# Arche-RoboCore.net
KiCad netlist of a schematic drawn in EAGLE
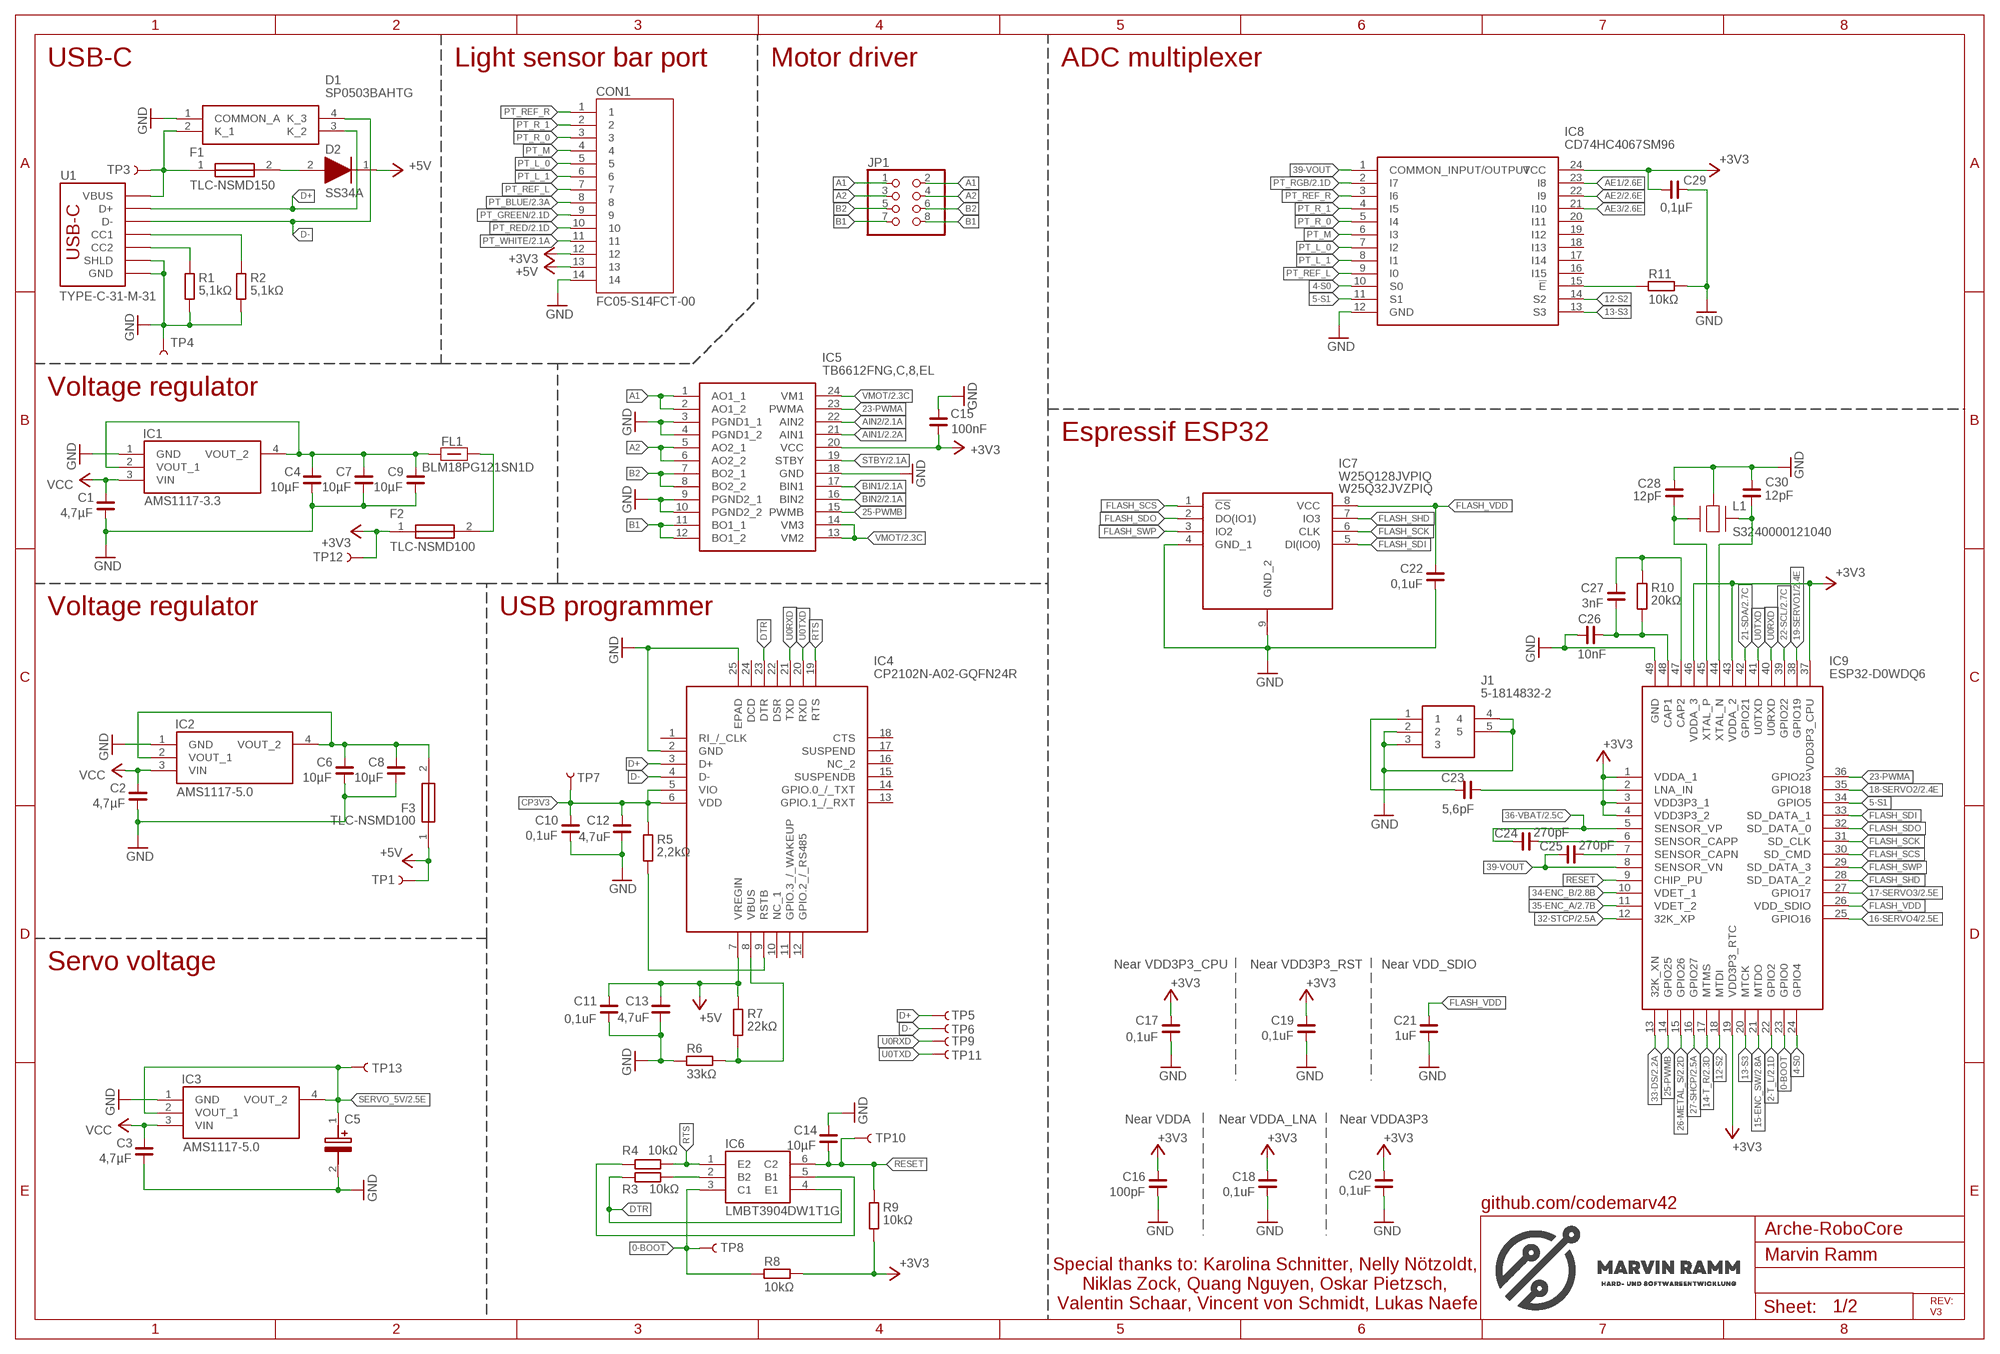
[diagram p0: schematic, sheet 1]
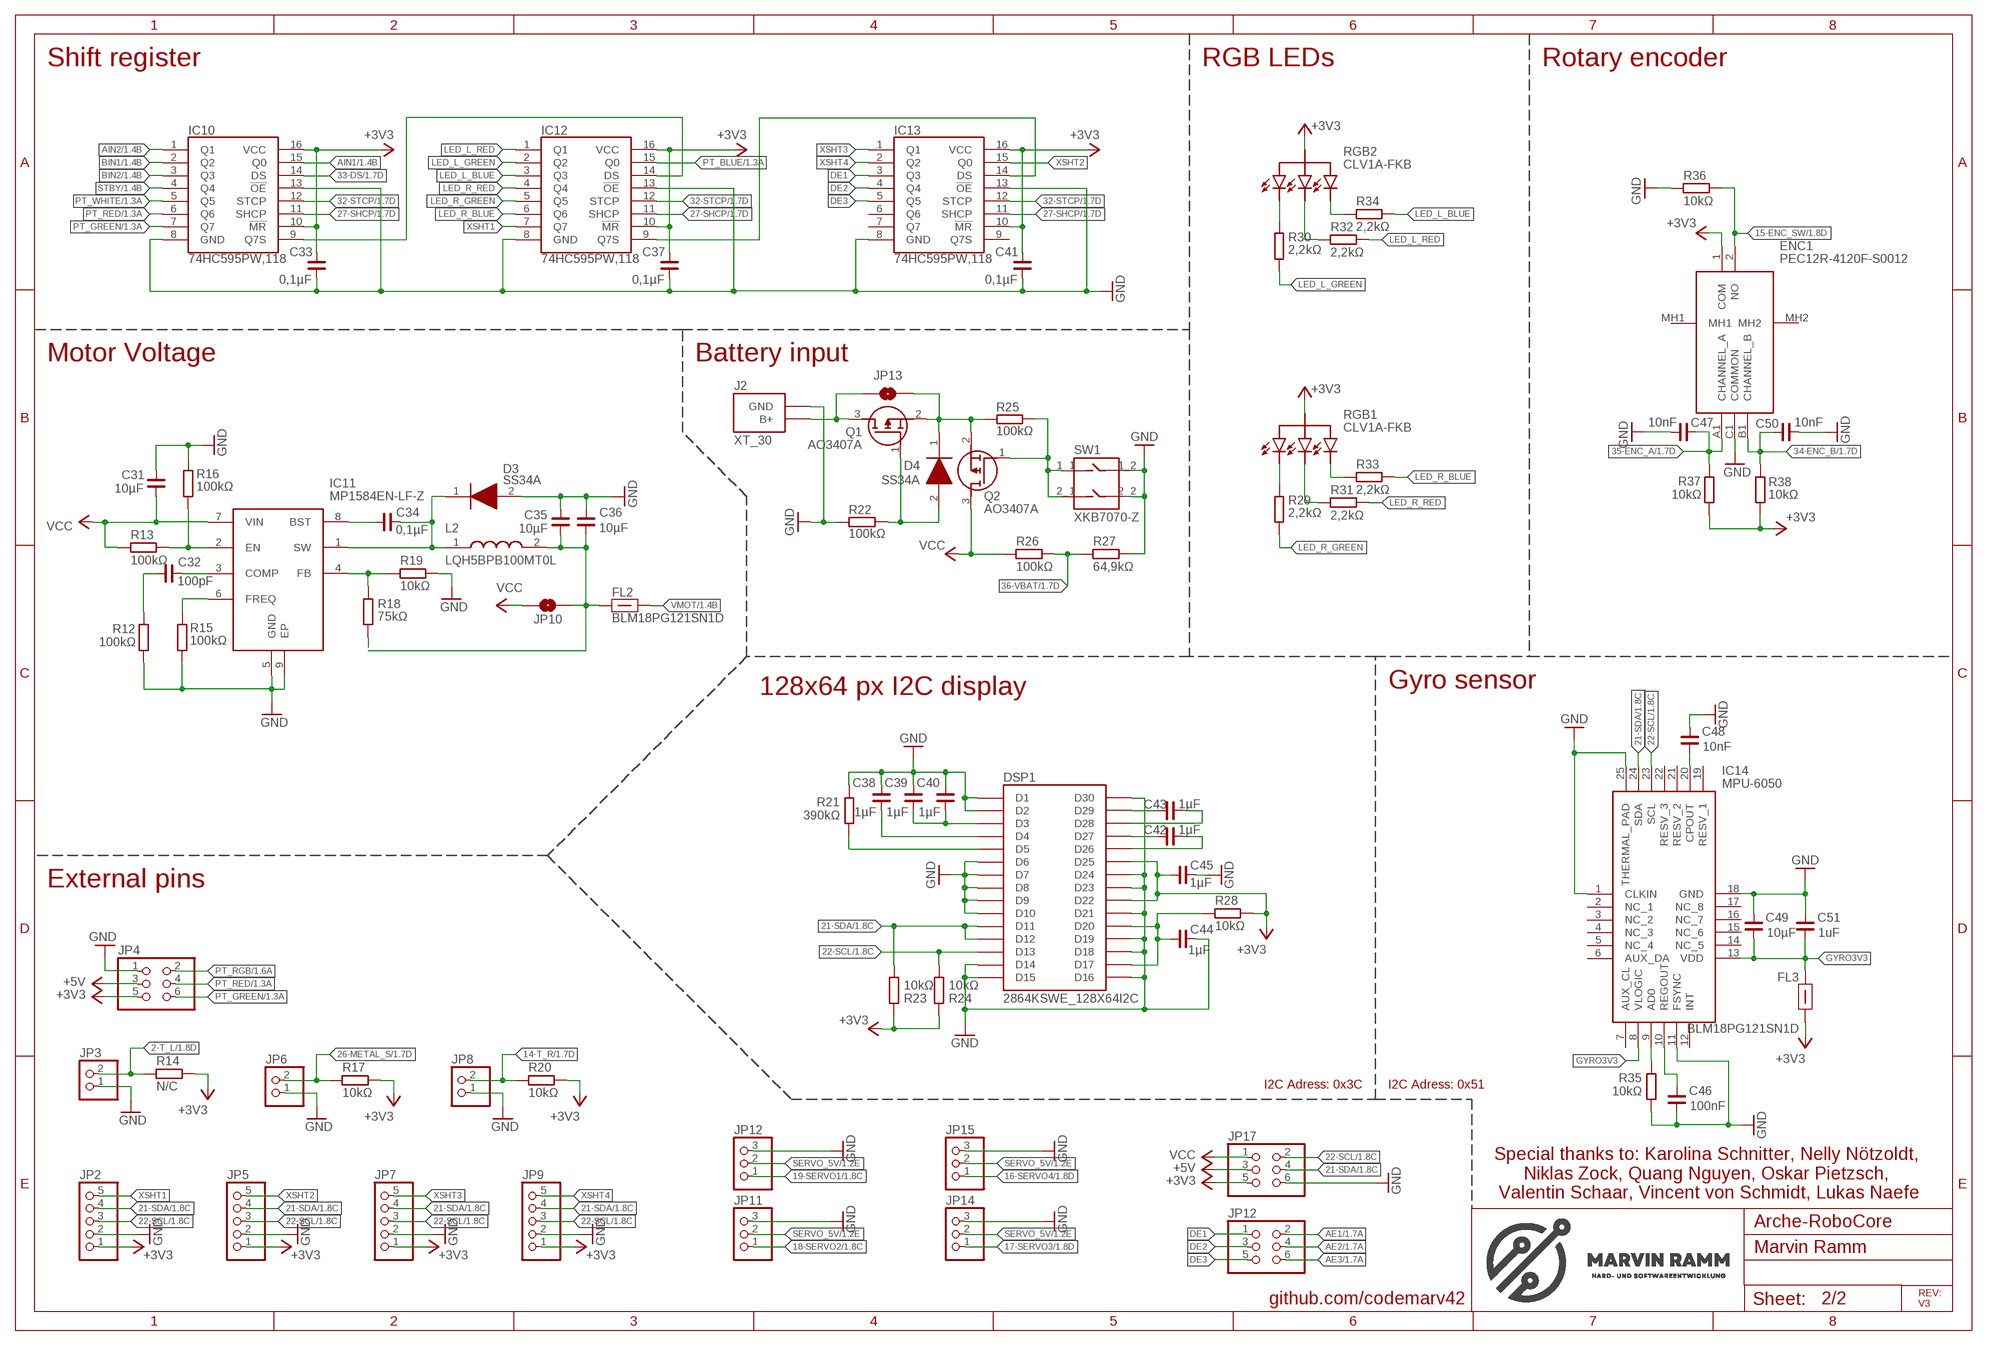
[diagram p1: schematic, sheet 2]

(export (version "E")
  (design (tool "Eeschema 10.0.6"))
  (components
    (comp (ref "C31")
      (value "10µF")
      (footprint "eagle-import:C0603")
      (libsource (lib "eagle-import") (part "C_0603"))
    )
    (comp (ref "C32")
      (value "100pF")
      (footprint "eagle-import:C0402")
      (libsource (lib "eagle-import") (part "C_0402"))
    )
    (comp (ref "C33")
      (value "0,1µF")
      (footprint "eagle-import:C0402")
      (libsource (lib "eagle-import") (part "C_0402"))
    )
    (comp (ref "C34")
      (value "0,1µF")
      (footprint "eagle-import:C0402")
      (libsource (lib "eagle-import") (part "C_0402"))
    )
    (comp (ref "C35")
      (value "10µF")
      (footprint "eagle-import:C0603")
      (libsource (lib "eagle-import") (part "C_0603"))
    )
    (comp (ref "C36")
      (value "10µF")
      (footprint "eagle-import:C0603")
      (libsource (lib "eagle-import") (part "C_0603"))
    )
    (comp (ref "C37")
      (value "0,1µF")
      (footprint "eagle-import:C0402")
      (libsource (lib "eagle-import") (part "C_0402"))
    )
    (comp (ref "C38")
      (value "1µF")
      (footprint "eagle-import:C0402")
      (libsource (lib "eagle-import") (part "C_0402"))
    )
    (comp (ref "C39")
      (value "1µF")
      (footprint "eagle-import:C0402")
      (libsource (lib "eagle-import") (part "C_0402"))
    )
    (comp (ref "C40")
      (value "1µF")
      (footprint "eagle-import:C0402")
      (libsource (lib "eagle-import") (part "C_0402"))
    )
    (comp (ref "C41")
      (value "0,1µF")
      (footprint "eagle-import:C0402")
      (libsource (lib "eagle-import") (part "C_0402"))
    )
    (comp (ref "C42")
      (value "1µF")
      (footprint "eagle-import:C0402")
      (libsource (lib "eagle-import") (part "C_0402"))
    )
    (comp (ref "C43")
      (value "1µF")
      (footprint "eagle-import:C0402")
      (libsource (lib "eagle-import") (part "C_0402"))
    )
    (comp (ref "C44")
      (value "1µF")
      (footprint "eagle-import:C0402")
      (libsource (lib "eagle-import") (part "C_0402"))
    )
    (comp (ref "C45")
      (value "1µF")
      (footprint "eagle-import:C0402")
      (libsource (lib "eagle-import") (part "C_0402"))
    )
    (comp (ref "C46")
      (value "100nF")
      (footprint "eagle-import:C0402")
      (libsource (lib "eagle-import") (part "C_0402"))
    )
    (comp (ref "C47")
      (value "10nF")
      (footprint "eagle-import:C0402")
      (libsource (lib "eagle-import") (part "C_0402"))
    )
    (comp (ref "C48")
      (value "10nF")
      (footprint "eagle-import:C0402")
      (libsource (lib "eagle-import") (part "C_0402"))
    )
    (comp (ref "C49")
      (value "10µF")
      (footprint "eagle-import:C0603")
      (libsource (lib "eagle-import") (part "C_0603"))
    )
    (comp (ref "C50")
      (value "10nF")
      (footprint "eagle-import:C0402")
      (libsource (lib "eagle-import") (part "C_0402"))
    )
    (comp (ref "C51")
      (value "1uF")
      (footprint "eagle-import:C0402")
      (libsource (lib "eagle-import") (part "C_0402"))
    )
    (comp (ref "D3")
      (value "SS34A")
      (footprint "eagle-import:DIOM5026X262N")
      (libsource (lib "eagle-import") (part "SS34A"))
    )
    (comp (ref "D4")
      (value "SS34A")
      (footprint "eagle-import:DIOM5026X262N")
      (libsource (lib "eagle-import") (part "SS34A"))
    )
    (comp (ref "DSP1")
      (value "2864KSWE_128X64I2C")
      (footprint "eagle-import:2864KSWE_128X64I2C")
      (libsource (lib "eagle-import") (part "2864KSWE_128X64I2C"))
    )
    (comp (ref "ENC1")
      (value "PEC12R-4230F-S0024")
      (footprint "eagle-import:PEC12R4230FS0024")
      (fields (field (name "MOUSER_PART_NUMBER") "652-PEC12R-4230F-S24"))
      (libsource (lib "eagle-import") (part "PEC12R-4230F-S0024"))
    )
    (comp (ref "FL2")
      (value "BLM18PG121SN1D")
      (footprint "eagle-import:BLM18AG102BH1D")
      (fields (field (name "MOUSER_PART_NUMBER") "81-BLM18PG121SN1D"))
      (libsource (lib "eagle-import") (part "BLM18PG121SN1D"))
    )
    (comp (ref "FL3")
      (value "BLM18PG121SN1D")
      (footprint "eagle-import:BLM18AG102BH1D")
      (fields (field (name "MOUSER_PART_NUMBER") "81-BLM18PG121SN1D"))
      (libsource (lib "eagle-import") (part "BLM18PG121SN1D"))
    )
    (comp (ref "IC10")
      (value "74HC595PW,118")
      (footprint "eagle-import:SOP65P640X110-16N")
      (fields (field (name "MOUSER_PART_NUMBER") "771-74HC595PW-T"))
      (libsource (lib "eagle-import") (part "74HC595PW,118"))
    )
    (comp (ref "IC11")
      (value "MP1584EN-LF-Z")
      (footprint "eagle-import:SOIC127P600X170-9N")
      (fields (field (name "MOUSER_PART_NUMBER") "946-MP1584ENLFZ"))
      (libsource (lib "eagle-import") (part "MP1584EN-LF-Z"))
    )
    (comp (ref "IC12")
      (value "74HC595PW,118")
      (footprint "eagle-import:SOP65P640X110-16N")
      (fields (field (name "MOUSER_PART_NUMBER") "771-74HC595PW-T"))
      (libsource (lib "eagle-import") (part "74HC595PW,118"))
    )
    (comp (ref "IC13")
      (value "74HC595PW,118")
      (footprint "eagle-import:SOP65P640X110-16N")
      (fields (field (name "MOUSER_PART_NUMBER") "771-74HC595PW-T"))
      (libsource (lib "eagle-import") (part "74HC595PW,118"))
    )
    (comp (ref "IC14")
      (value "MPU-6050")
      (footprint "eagle-import:QFN50P400X400X95-25N")
      (libsource (lib "eagle-import") (part "MPU-6050"))
    )
    (comp (ref "J2")
      (value "XT_30")
      (footprint "eagle-import:XT_30")
      (libsource (lib "eagle-import") (part "XT_30"))
    )
    (comp (ref "JP2")
      (value "PINHD-1X5")
      (footprint "eagle-import:1X05")
      (libsource (lib "eagle-import") (part "PINHD-1X5"))
    )
    (comp (ref "JP3")
      (value "PINHD-1X2")
      (footprint "eagle-import:1X02")
      (libsource (lib "eagle-import") (part "PINHD-1X2"))
    )
    (comp (ref "JP4")
      (value "PINHD-2X3")
      (footprint "eagle-import:2X03")
      (libsource (lib "eagle-import") (part "PINHD-2X3"))
    )
    (comp (ref "JP5")
      (value "PINHD-1X5")
      (footprint "eagle-import:1X05")
      (libsource (lib "eagle-import") (part "PINHD-1X5"))
    )
    (comp (ref "JP6")
      (value "PINHD-1X2")
      (footprint "eagle-import:1X02")
      (libsource (lib "eagle-import") (part "PINHD-1X2"))
    )
    (comp (ref "JP7")
      (value "PINHD-1X5")
      (footprint "eagle-import:1X05")
      (libsource (lib "eagle-import") (part "PINHD-1X5"))
    )
    (comp (ref "JP8")
      (value "PINHD-1X2")
      (footprint "eagle-import:1X02")
      (libsource (lib "eagle-import") (part "PINHD-1X2"))
    )
    (comp (ref "JP9")
      (value "PINHD-1X5")
      (footprint "eagle-import:1X05")
      (libsource (lib "eagle-import") (part "PINHD-1X5"))
    )
    (comp (ref "JP10")
      (value "JUMPER-SMT_2_NO_SILK")
      (footprint "eagle-import:SMT-JUMPER_2_NO_SILK")
      (libsource (lib "eagle-import") (part "JUMPER-SMT_2_NO_SILK"))
    )
    (comp (ref "JP11")
      (value "PINHD-1X3")
      (footprint "eagle-import:1X03")
      (libsource (lib "eagle-import") (part "PINHD-1X3"))
    )
    (comp (ref "JP12")
      (value "PINHD-1X3")
      (footprint "eagle-import:1X03")
      (libsource (lib "eagle-import") (part "PINHD-1X3"))
    )
    (comp (ref "JP13")
      (value "JUMPER-SMT_2_NO_SILK")
      (footprint "eagle-import:SMT-JUMPER_2_NO_SILK")
      (libsource (lib "eagle-import") (part "JUMPER-SMT_2_NO_SILK"))
    )
    (comp (ref "JP14")
      (value "PINHD-1X3")
      (footprint "eagle-import:1X03")
      (libsource (lib "eagle-import") (part "PINHD-1X3"))
    )
    (comp (ref "JP15")
      (value "PINHD-1X3")
      (footprint "eagle-import:1X03")
      (libsource (lib "eagle-import") (part "PINHD-1X3"))
    )
    (comp (ref "JP16")
      (value "PINHD-2X3")
      (footprint "eagle-import:2X03")
      (libsource (lib "eagle-import") (part "PINHD-2X3"))
    )
    (comp (ref "JP17")
      (value "PINHD-2X3")
      (footprint "eagle-import:2X03")
      (libsource (lib "eagle-import") (part "PINHD-2X3"))
    )
    (comp (ref "L2")
      (value "LQH5BPB100MT0L")
      (footprint "eagle-import:LQH5BPB100MT0L")
      (fields (field (name "MOUSER_PART_NUMBER") "81-LQH5BPB100MT0L"))
      (libsource (lib "eagle-import") (part "LQH5BPB100MT0L"))
    )
    (comp (ref "Q1")
      (value "AO3407A")
      (footprint "eagle-import:SOT95P280X125-3N")
      (libsource (lib "eagle-import") (part "AO3407A"))
    )
    (comp (ref "Q2")
      (value "AO3407A")
      (footprint "eagle-import:SOT95P280X125-3N")
      (libsource (lib "eagle-import") (part "AO3407A"))
    )
    (comp (ref "R12")
      (value "100kΩ")
      (footprint "eagle-import:R0402")
      (libsource (lib "eagle-import") (part "R_0402"))
    )
    (comp (ref "R13")
      (value "100kΩ")
      (footprint "eagle-import:R0402")
      (libsource (lib "eagle-import") (part "R_0402"))
    )
    (comp (ref "R14")
      (value "N/C")
      (footprint "eagle-import:R0402")
      (libsource (lib "eagle-import") (part "R_0402"))
    )
    (comp (ref "R15")
      (value "100kΩ")
      (footprint "eagle-import:R0402")
      (libsource (lib "eagle-import") (part "R_0402"))
    )
    (comp (ref "R16")
      (value "100kΩ")
      (footprint "eagle-import:R0402")
      (libsource (lib "eagle-import") (part "R_0402"))
    )
    (comp (ref "R17")
      (value "10kΩ")
      (footprint "eagle-import:R0402")
      (libsource (lib "eagle-import") (part "R_0402"))
    )
    (comp (ref "R18")
      (value "75kΩ")
      (footprint "eagle-import:R0402")
      (libsource (lib "eagle-import") (part "R_0402"))
    )
    (comp (ref "R19")
      (value "10kΩ")
      (footprint "eagle-import:R0402")
      (libsource (lib "eagle-import") (part "R_0402"))
    )
    (comp (ref "R20")
      (value "10kΩ")
      (footprint "eagle-import:R0402")
      (libsource (lib "eagle-import") (part "R_0402"))
    )
    (comp (ref "R21")
      (value "390kΩ")
      (footprint "eagle-import:R0402")
      (libsource (lib "eagle-import") (part "R_0402"))
    )
    (comp (ref "R22")
      (value "100kΩ")
      (footprint "eagle-import:R0402")
      (libsource (lib "eagle-import") (part "R_0402"))
    )
    (comp (ref "R23")
      (value "10kΩ")
      (footprint "eagle-import:R0402")
      (libsource (lib "eagle-import") (part "R_0402"))
    )
    (comp (ref "R24")
      (value "10kΩ")
      (footprint "eagle-import:R0402")
      (libsource (lib "eagle-import") (part "R_0402"))
    )
    (comp (ref "R25")
      (value "100kΩ")
      (footprint "eagle-import:R0402")
      (libsource (lib "eagle-import") (part "R_0402"))
    )
    (comp (ref "R26")
      (value "100kΩ")
      (footprint "eagle-import:R0402")
      (libsource (lib "eagle-import") (part "R_0402"))
    )
    (comp (ref "R27")
      (value "64,9kΩ")
      (footprint "eagle-import:R0402")
      (libsource (lib "eagle-import") (part "R_0402"))
    )
    (comp (ref "R28")
      (value "10kΩ")
      (footprint "eagle-import:R0402")
      (libsource (lib "eagle-import") (part "R_0402"))
    )
    (comp (ref "R29")
      (value "2,2kΩ")
      (footprint "eagle-import:R0402")
      (libsource (lib "eagle-import") (part "R_0402"))
    )
    (comp (ref "R30")
      (value "2,2kΩ")
      (footprint "eagle-import:R0402")
      (libsource (lib "eagle-import") (part "R_0402"))
    )
    (comp (ref "R31")
      (value "2,2kΩ")
      (footprint "eagle-import:R0402")
      (libsource (lib "eagle-import") (part "R_0402"))
    )
    (comp (ref "R32")
      (value "2,2kΩ")
      (footprint "eagle-import:R0402")
      (libsource (lib "eagle-import") (part "R_0402"))
    )
    (comp (ref "R33")
      (value "2,2kΩ")
      (footprint "eagle-import:R0402")
      (libsource (lib "eagle-import") (part "R_0402"))
    )
    (comp (ref "R34")
      (value "2,2kΩ")
      (footprint "eagle-import:R0402")
      (libsource (lib "eagle-import") (part "R_0402"))
    )
    (comp (ref "R35")
      (value "10kΩ")
      (footprint "eagle-import:R0402")
      (libsource (lib "eagle-import") (part "R_0402"))
    )
    (comp (ref "R36")
      (value "10kΩ")
      (footprint "eagle-import:R0402")
      (libsource (lib "eagle-import") (part "R_0402"))
    )
    (comp (ref "R37")
      (value "10kΩ")
      (footprint "eagle-import:R0402")
      (libsource (lib "eagle-import") (part "R_0402"))
    )
    (comp (ref "R38")
      (value "10kΩ")
      (footprint "eagle-import:R0402")
      (libsource (lib "eagle-import") (part "R_0402"))
    )
    (comp (ref "RGB1")
      (value "RGBLED")
      (footprint "eagle-import:RGBLED")
      (libsource (lib "eagle-import") (part "RGBLED"))
    )
    (comp (ref "RGB2")
      (value "RGBLED")
      (footprint "eagle-import:RGBLED")
      (libsource (lib "eagle-import") (part "RGBLED"))
    )
    (comp (ref "SW1")
      (value "XKB7070-Z")
      (footprint "eagle-import:XKB7070-Z")
      (libsource (lib "eagle-import") (part "XKB7070-Z"))
    )
    (comp (ref "C1")
      (value "4,7µF")
      (footprint "eagle-import:C0603")
      (libsource (lib "eagle-import") (part "C_0603"))
    )
    (comp (ref "C2")
      (value "4,7µF")
      (footprint "eagle-import:C0603")
      (libsource (lib "eagle-import") (part "C_0603"))
    )
    (comp (ref "C3")
      (value "4,7µF")
      (footprint "eagle-import:C0603")
      (libsource (lib "eagle-import") (part "C_0603"))
    )
    (comp (ref "C4")
      (value "10µF")
      (footprint "eagle-import:C0603")
      (libsource (lib "eagle-import") (part "C_0603"))
    )
    (comp (ref "C5")
      (value "UUD1C151MCL1GS")
      (footprint "eagle-import:CAPAE660X800N")
      (fields (field (name "MOUSER_PART_NUMBER") "647-UUD1C151MCL"))
      (libsource (lib "eagle-import") (part "UUD1C151MCL1GS"))
    )
    (comp (ref "C6")
      (value "10µF")
      (footprint "eagle-import:C0603")
      (libsource (lib "eagle-import") (part "C_0603"))
    )
    (comp (ref "C7")
      (value "10µF")
      (footprint "eagle-import:C0603")
      (libsource (lib "eagle-import") (part "C_0603"))
    )
    (comp (ref "C8")
      (value "10µF")
      (footprint "eagle-import:C0603")
      (libsource (lib "eagle-import") (part "C_0603"))
    )
    (comp (ref "C9")
      (value "10µF")
      (footprint "eagle-import:C0603")
      (libsource (lib "eagle-import") (part "C_0603"))
    )
    (comp (ref "C10")
      (value "0,1uF")
      (footprint "eagle-import:C0402")
      (libsource (lib "eagle-import") (part "C_0402"))
    )
    (comp (ref "C11")
      (value "0,1uF")
      (footprint "eagle-import:C0402")
      (libsource (lib "eagle-import") (part "C_0402"))
    )
    (comp (ref "C12")
      (value "4,7uF")
      (footprint "eagle-import:C0402")
      (libsource (lib "eagle-import") (part "C_0402"))
    )
    (comp (ref "C13")
      (value "4,7uF")
      (footprint "eagle-import:C0402")
      (libsource (lib "eagle-import") (part "C_0402"))
    )
    (comp (ref "C14")
      (value "10µF")
      (footprint "eagle-import:C0603")
      (libsource (lib "eagle-import") (part "C_0603"))
    )
    (comp (ref "C15")
      (value "100nF")
      (footprint "eagle-import:C0402")
      (libsource (lib "eagle-import") (part "C_0402"))
    )
    (comp (ref "C16")
      (value "100pF")
      (footprint "eagle-import:C0402")
      (libsource (lib "eagle-import") (part "C_0402"))
    )
    (comp (ref "C17")
      (value "0,1uF")
      (footprint "eagle-import:C0402")
      (libsource (lib "eagle-import") (part "C_0402"))
    )
    (comp (ref "C18")
      (value "0,1uF")
      (footprint "eagle-import:C0402")
      (libsource (lib "eagle-import") (part "C_0402"))
    )
    (comp (ref "C19")
      (value "0,1uF")
      (footprint "eagle-import:C0402")
      (libsource (lib "eagle-import") (part "C_0402"))
    )
    (comp (ref "C20")
      (value "0,1uF")
      (footprint "eagle-import:C0402")
      (libsource (lib "eagle-import") (part "C_0402"))
    )
    (comp (ref "C21")
      (value "1uF")
      (footprint "eagle-import:C0402")
      (libsource (lib "eagle-import") (part "C_0402"))
    )
    (comp (ref "C22")
      (value "0,1uF")
      (footprint "eagle-import:C0402")
      (libsource (lib "eagle-import") (part "C_0402"))
    )
    (comp (ref "C23")
      (value "5,6pF")
      (footprint "eagle-import:C0402")
      (libsource (lib "eagle-import") (part "C_0402"))
    )
    (comp (ref "C24")
      (value "270pF")
      (footprint "eagle-import:C0402")
      (libsource (lib "eagle-import") (part "C_0402"))
    )
    (comp (ref "C25")
      (value "270pF")
      (footprint "eagle-import:C0402")
      (libsource (lib "eagle-import") (part "C_0402"))
    )
    (comp (ref "C26")
      (value "10nF")
      (footprint "eagle-import:C0402")
      (libsource (lib "eagle-import") (part "C_0402"))
    )
    (comp (ref "C27")
      (value "3nF")
      (footprint "eagle-import:C0402")
      (libsource (lib "eagle-import") (part "C_0402"))
    )
    (comp (ref "C28")
      (value "12pF")
      (footprint "eagle-import:C0402")
      (libsource (lib "eagle-import") (part "C_0402"))
    )
    (comp (ref "C29")
      (value "0,1µF")
      (footprint "eagle-import:C0402")
      (libsource (lib "eagle-import") (part "C_0402"))
    )
    (comp (ref "C30")
      (value "12pF")
      (footprint "eagle-import:C0402")
      (libsource (lib "eagle-import") (part "C_0402"))
    )
    (comp (ref "CON1")
      (value "FC05-S14FCT-00")
      (footprint "eagle-import:FC05-S14FCT-00")
      (libsource (lib "eagle-import") (part "FC05-S14FCT-00"))
    )
    (comp (ref "D1")
      (value "SP0503BAHTG")
      (footprint "eagle-import:SP0503BAHTG")
      (fields (field (name "MOUSER_PART_NUMBER") "576-SP0503BAHTG"))
      (libsource (lib "eagle-import") (part "SP0503BAHTG"))
    )
    (comp (ref "D2")
      (value "SS34A")
      (footprint "eagle-import:DIOM5026X262N")
      (libsource (lib "eagle-import") (part "SS34A"))
    )
    (comp (ref "F1")
      (value "NANOSMDC020F-2")
      (footprint "eagle-import:FUSC3216X82N")
      (fields (field (name "MOUSER_PART_NUMBER") "650-NANOSMDC020F-2"))
      (libsource (lib "eagle-import") (part "NANOSMDC020F-2"))
    )
    (comp (ref "F2")
      (value "NANOSMDC020F-2")
      (footprint "eagle-import:FUSC3216X82N")
      (fields (field (name "MOUSER_PART_NUMBER") "650-NANOSMDC020F-2"))
      (libsource (lib "eagle-import") (part "NANOSMDC020F-2"))
    )
    (comp (ref "F3")
      (value "NANOSMDC020F-2")
      (footprint "eagle-import:FUSC3216X82N")
      (fields (field (name "MOUSER_PART_NUMBER") "650-NANOSMDC020F-2"))
      (libsource (lib "eagle-import") (part "NANOSMDC020F-2"))
    )
    (comp (ref "FL1")
      (value "BLM18PG121SN1D")
      (footprint "eagle-import:BLM18AG102BH1D")
      (fields (field (name "MOUSER_PART_NUMBER") "81-BLM18PG121SN1D"))
      (libsource (lib "eagle-import") (part "BLM18PG121SN1D"))
    )
    (comp (ref "IC1")
      (value "AMS1117-3.3")
      (footprint "eagle-import:SOT229P700X180-4N")
      (libsource (lib "eagle-import") (part "AMS1117-3.3"))
    )
    (comp (ref "IC2")
      (value "AMS1117-3.3")
      (footprint "eagle-import:SOT229P700X180-4N")
      (libsource (lib "eagle-import") (part "AMS1117-3.3"))
    )
    (comp (ref "IC3")
      (value "AMS1117-3.3")
      (footprint "eagle-import:SOT229P700X180-4N")
      (libsource (lib "eagle-import") (part "AMS1117-3.3"))
    )
    (comp (ref "IC4")
      (value "CP2102N-A02-GQFN24R")
      (footprint "eagle-import:QFN50P400X400X80-25N")
      (fields (field (name "MOUSER_PART_NUMBER") "634-CP2102NA02QFN24R") (field (name "SPICEPREFIX") "X"))
      (libsource (lib "eagle-import") (part "CP2102N-A02-GQFN24R"))
    )
    (comp (ref "IC5")
      (value "TB6612FNG,C,8,EL")
      (footprint "eagle-import:SOP65P760X160-24N")
      (fields (field (name "MOUSER_PART_NUMBER") "757-TB6612FNGC8EL"))
      (libsource (lib "eagle-import") (part "TB6612FNG,C,8,EL"))
    )
    (comp (ref "IC6")
      (value "MMDT3904-TP")
      (footprint "eagle-import:SOT65P230X120-6N")
      (fields (field (name "MOUSER_PART_NUMBER") "833-MMDT3904-TP"))
      (libsource (lib "eagle-import") (part "MMDT3904-TP"))
    )
    (comp (ref "IC7")
      (value "W25Q128JVPIQ")
      (footprint "eagle-import:SON127P800X600X80-9N")
      (fields (field (name "MOUSER_PART_NUMBER") "454-W25Q128JVPIQ"))
      (libsource (lib "eagle-import") (part "W25Q128JVPIQ"))
    )
    (comp (ref "IC8")
      (value "CD74HC4067SM96")
      (footprint "eagle-import:SOP65P780X200-24N")
      (fields (field (name "MOUSER_PART_NUMBER") "595-CD74HC4067SM96"))
      (libsource (lib "eagle-import") (part "CD74HC4067SM96"))
    )
    (comp (ref "IC9")
      (value "ESP32-D0WDQ6")
      (footprint "eagle-import:QFN40P600X600X90-49N")
      (fields (field (name "MOUSER_PART_NUMBER") "356-ESP32-D0WDQ6"))
      (libsource (lib "eagle-import") (part "ESP32-D0WDQ6"))
    )
    (comp (ref "J1")
      (value "5-1814832-2")
      (footprint "eagle-import:518148322")
      (fields (field (name "MOUSER_PART_NUMBER") "571-5-1814832-2"))
      (libsource (lib "eagle-import") (part "5-1814832-2"))
    )
    (comp (ref "JP1")
      (value "PINHD-2X4")
      (footprint "eagle-import:2X04")
      (libsource (lib "eagle-import") (part "PINHD-2X4"))
    )
    (comp (ref "L1")
      (value "SMD-3225_4P16MHZ_20PF_10PPM_-4")
      (footprint "eagle-import:SMD3225_4P16MHZ20PF10PPM4085")
      (fields (field (name "MANUFACTURER_PART_NUMBER") "SMD-3225_4P16MHZ 20PF 10PPM -40~+85℃"))
      (libsource (lib "eagle-import") (part "SMD-3225_4P16MHZ_20PF_10PPM_-4"))
    )
    (comp (ref "R1")
      (value "5,1kΩ")
      (footprint "eagle-import:R0402")
      (libsource (lib "eagle-import") (part "R_0402"))
    )
    (comp (ref "R2")
      (value "5,1kΩ")
      (footprint "eagle-import:R0402")
      (libsource (lib "eagle-import") (part "R_0402"))
    )
    (comp (ref "R3")
      (value "10kΩ")
      (footprint "eagle-import:R0402")
      (libsource (lib "eagle-import") (part "R_0402"))
    )
    (comp (ref "R4")
      (value "10kΩ")
      (footprint "eagle-import:R0402")
      (libsource (lib "eagle-import") (part "R_0402"))
    )
    (comp (ref "R5")
      (value "2,2kΩ")
      (footprint "eagle-import:R0402")
      (libsource (lib "eagle-import") (part "R_0402"))
    )
    (comp (ref "R6")
      (value "33kΩ")
      (footprint "eagle-import:R0402")
      (libsource (lib "eagle-import") (part "R_0402"))
    )
    (comp (ref "R7")
      (value "22kΩ")
      (footprint "eagle-import:R0402")
      (libsource (lib "eagle-import") (part "R_0402"))
    )
    (comp (ref "R8")
      (value "10kΩ")
      (footprint "eagle-import:R0402")
      (libsource (lib "eagle-import") (part "R_0402"))
    )
    (comp (ref "R9")
      (value "10kΩ")
      (footprint "eagle-import:R0402")
      (libsource (lib "eagle-import") (part "R_0402"))
    )
    (comp (ref "R10")
      (value "20kΩ")
      (footprint "eagle-import:R0402")
      (libsource (lib "eagle-import") (part "R_0402"))
    )
    (comp (ref "R11")
      (value "10kΩ")
      (footprint "eagle-import:R0402")
      (libsource (lib "eagle-import") (part "R_0402"))
    )
    (comp (ref "TP1")
      (value "TEST-POINT3X5")
      (footprint "eagle-import:PAD.03X.05")
      (libsource (lib "eagle-import") (part "TEST-POINT3X5"))
    )
    (comp (ref "TP3")
      (value "TEST-POINT3X5")
      (footprint "eagle-import:PAD.03X.05")
      (libsource (lib "eagle-import") (part "TEST-POINT3X5"))
    )
    (comp (ref "TP4")
      (value "TEST-POINT3X5")
      (footprint "eagle-import:PAD.03X.05")
      (libsource (lib "eagle-import") (part "TEST-POINT3X5"))
    )
    (comp (ref "TP5")
      (value "TEST-POINT3X5")
      (footprint "eagle-import:PAD.03X.05")
      (libsource (lib "eagle-import") (part "TEST-POINT3X5"))
    )
    (comp (ref "TP6")
      (value "TEST-POINT3X5")
      (footprint "eagle-import:PAD.03X.05")
      (libsource (lib "eagle-import") (part "TEST-POINT3X5"))
    )
    (comp (ref "TP7")
      (value "TEST-POINT3X5")
      (footprint "eagle-import:PAD.03X.05")
      (libsource (lib "eagle-import") (part "TEST-POINT3X5"))
    )
    (comp (ref "TP8")
      (value "TEST-POINT3X5")
      (footprint "eagle-import:PAD.03X.05")
      (libsource (lib "eagle-import") (part "TEST-POINT3X5"))
    )
    (comp (ref "TP9")
      (value "TEST-POINT3X5")
      (footprint "eagle-import:PAD.03X.05")
      (libsource (lib "eagle-import") (part "TEST-POINT3X5"))
    )
    (comp (ref "TP10")
      (value "TEST-POINT3X5")
      (footprint "eagle-import:PAD.03X.05")
      (libsource (lib "eagle-import") (part "TEST-POINT3X5"))
    )
    (comp (ref "TP11")
      (value "TEST-POINT3X5")
      (footprint "eagle-import:PAD.03X.05")
      (libsource (lib "eagle-import") (part "TEST-POINT3X5"))
    )
    (comp (ref "TP12")
      (value "TEST-POINT3X5")
      (footprint "eagle-import:PAD.03X.05")
      (libsource (lib "eagle-import") (part "TEST-POINT3X5"))
    )
    (comp (ref "TP13")
      (value "TEST-POINT3X5")
      (footprint "eagle-import:PAD.03X.05")
      (libsource (lib "eagle-import") (part "TEST-POINT3X5"))
    )
    (comp (ref "U1")
      (value "TYPE-C-31-M-14")
      (footprint "eagle-import:TYPE-C-31-M-14_HRO")
      (fields (field (name "COPYRIGHT") "Copyright (C) 2018 Accelerated Designs. All rights reserved"))
      (libsource (lib "eagle-import") (part "TYPE-C-31-M-14"))
    )
  )
  (nets
    (net (code "1") (name "+3V3") (class "Default")
      (node (ref "C15") (pin "1") (pinfunction "1_1") (pintype "passive"))
      (node (ref "C16") (pin "2") (pinfunction "2_2") (pintype "passive"))
      (node (ref "C17") (pin "2") (pinfunction "2_2") (pintype "passive"))
      (node (ref "C18") (pin "2") (pinfunction "2_2") (pintype "passive"))
      (node (ref "C19") (pin "2") (pinfunction "2_2") (pintype "passive"))
      (node (ref "C20") (pin "2") (pinfunction "2_2") (pintype "passive"))
      (node (ref "C29") (pin "1") (pinfunction "1_1") (pintype "passive"))
      (node (ref "C33") (pin "1") (pinfunction "1_1") (pintype "passive"))
      (node (ref "C37") (pin "1") (pinfunction "1_1") (pintype "passive"))
      (node (ref "C41") (pin "1") (pinfunction "1_1") (pintype "passive"))
      (node (ref "C45") (pin "1") (pinfunction "1_1") (pintype "passive"))
      (node (ref "CON1") (pin "12") (pinfunction "12_12") (pintype "bidirectional"))
      (node (ref "DSP1") (pin "D22") (pinfunction "D22_D22") (pintype "bidirectional"))
      (node (ref "DSP1") (pin "D25") (pinfunction "D25_D25") (pintype "bidirectional"))
      (node (ref "ENC1") (pin "1") (pinfunction "COM_1") (pintype "bidirectional"))
      (node (ref "F2") (pin "1") (pinfunction "1_1") (pintype "bidirectional"))
      (node (ref "FL3") (pin "1") (pinfunction "1_1") (pintype "bidirectional"))
      (node (ref "IC10") (pin "10") (pinfunction "~{MR}_10") (pintype "bidirectional"))
      (node (ref "IC10") (pin "16") (pinfunction "VCC_16") (pintype "bidirectional"))
      (node (ref "IC12") (pin "10") (pinfunction "~{MR}_10") (pintype "bidirectional"))
      (node (ref "IC12") (pin "16") (pinfunction "VCC_16") (pintype "bidirectional"))
      (node (ref "IC13") (pin "10") (pinfunction "~{MR}_10") (pintype "bidirectional"))
      (node (ref "IC13") (pin "16") (pinfunction "VCC_16") (pintype "bidirectional"))
      (node (ref "IC5") (pin "20") (pinfunction "VCC_20") (pintype "bidirectional"))
      (node (ref "IC8") (pin "24") (pinfunction "VCC_24") (pintype "bidirectional"))
      (node (ref "IC9") (pin "1") (pinfunction "VDDA_1_1") (pintype "bidirectional"))
      (node (ref "IC9") (pin "19") (pinfunction "VDD3P3_RTC_19") (pintype "bidirectional"))
      (node (ref "IC9") (pin "3") (pinfunction "VDD3P3_1_3") (pintype "bidirectional"))
      (node (ref "IC9") (pin "37") (pinfunction "VDD3P3_CPU_37") (pintype "bidirectional"))
      (node (ref "IC9") (pin "4") (pinfunction "VDD3P3_2_4") (pintype "bidirectional"))
      (node (ref "IC9") (pin "43") (pinfunction "VDDA_2_43") (pintype "bidirectional"))
      (node (ref "IC9") (pin "46") (pinfunction "VDDA_3_46") (pintype "bidirectional"))
      (node (ref "JP17") (pin "5") (pinfunction "5_5") (pintype "passive"))
      (node (ref "JP2") (pin "1") (pinfunction "1_1") (pintype "passive"))
      (node (ref "JP4") (pin "5") (pinfunction "5_5") (pintype "passive"))
      (node (ref "JP5") (pin "1") (pinfunction "1_1") (pintype "passive"))
      (node (ref "JP7") (pin "1") (pinfunction "1_1") (pintype "passive"))
      (node (ref "JP9") (pin "1") (pinfunction "1_1") (pintype "passive"))
      (node (ref "R14") (pin "2") (pinfunction "2_2") (pintype "passive"))
      (node (ref "R17") (pin "2") (pinfunction "2_2") (pintype "passive"))
      (node (ref "R20") (pin "2") (pinfunction "2_2") (pintype "passive"))
      (node (ref "R23") (pin "2") (pinfunction "2_2") (pintype "passive"))
      (node (ref "R24") (pin "2") (pinfunction "2_2") (pintype "passive"))
      (node (ref "R28") (pin "2") (pinfunction "2_2") (pintype "passive"))
      (node (ref "R37") (pin "1") (pinfunction "1_1") (pintype "passive"))
      (node (ref "R38") (pin "1") (pinfunction "1_1") (pintype "passive"))
      (node (ref "R8") (pin "1") (pinfunction "1_1") (pintype "passive"))
      (node (ref "R9") (pin "2") (pinfunction "2_2") (pintype "passive"))
      (node (ref "RGB1") (pin "+5V") (pinfunction "+5V_+5V") (pintype "bidirectional"))
      (node (ref "RGB2") (pin "+5V") (pinfunction "+5V_+5V") (pintype "bidirectional"))
      (node (ref "TP12") (pin "1") (pinfunction "1_1") (pintype "bidirectional"))
    )
    (net (code "2") (name "+5V") (class "Default")
      (node (ref "C11") (pin "2") (pinfunction "2_2") (pintype "passive"))
      (node (ref "C13") (pin "2") (pinfunction "2_2") (pintype "passive"))
      (node (ref "CON1") (pin "13") (pinfunction "13_13") (pintype "bidirectional"))
      (node (ref "D2") (pin "1") (pinfunction "K_1") (pintype "bidirectional"))
      (node (ref "F3") (pin "1") (pinfunction "1_1") (pintype "bidirectional"))
      (node (ref "IC4") (pin "7") (pinfunction "VREGIN_7") (pintype "bidirectional"))
      (node (ref "JP17") (pin "3") (pinfunction "3_3") (pintype "passive"))
      (node (ref "JP4") (pin "3") (pinfunction "3_3") (pintype "passive"))
      (node (ref "R7") (pin "1") (pinfunction "1_1") (pintype "passive"))
      (node (ref "TP1") (pin "1") (pinfunction "1_1") (pintype "bidirectional"))
    )
    (net (code "3") (name "0-BOOT") (class "Default")
      (node (ref "IC6") (pin "3") (pinfunction "C1_3") (pintype "bidirectional"))
      (node (ref "IC9") (pin "23") (pinfunction "GPIO0_23") (pintype "bidirectional"))
      (node (ref "R8") (pin "2") (pinfunction "2_2") (pintype "passive"))
      (node (ref "TP8") (pin "1") (pinfunction "1_1") (pintype "bidirectional"))
    )
    (net (code "4") (name "2-T_L") (class "Default")
      (node (ref "IC9") (pin "22") (pinfunction "GPIO2_22") (pintype "bidirectional"))
      (node (ref "JP3") (pin "2") (pinfunction "2_2") (pintype "passive"))
      (node (ref "R14") (pin "1") (pinfunction "1_1") (pintype "passive"))
    )
    (net (code "5") (name "4-S0") (class "Default")
      (node (ref "IC8") (pin "10") (pinfunction "S0_10") (pintype "bidirectional"))
      (node (ref "IC9") (pin "24") (pinfunction "GPIO4_24") (pintype "bidirectional"))
    )
    (net (code "6") (name "5-S1") (class "Default")
      (node (ref "IC8") (pin "11") (pinfunction "S1_11") (pintype "bidirectional"))
      (node (ref "IC9") (pin "34") (pinfunction "GPIO5_34") (pintype "bidirectional"))
    )
    (net (code "7") (name "12-S2") (class "Default")
      (node (ref "IC8") (pin "14") (pinfunction "S2_14") (pintype "bidirectional"))
      (node (ref "IC9") (pin "18") (pinfunction "MTDI_18") (pintype "bidirectional"))
    )
    (net (code "8") (name "13-S3") (class "Default")
      (node (ref "IC8") (pin "13") (pinfunction "S3_13") (pintype "bidirectional"))
      (node (ref "IC9") (pin "20") (pinfunction "MTCK_20") (pintype "bidirectional"))
    )
    (net (code "9") (name "14-T_R") (class "Default")
      (node (ref "IC9") (pin "17") (pinfunction "MTMS_17") (pintype "bidirectional"))
      (node (ref "JP8") (pin "2") (pinfunction "2_2") (pintype "passive"))
      (node (ref "R20") (pin "1") (pinfunction "1_1") (pintype "passive"))
    )
    (net (code "10") (name "15-ENC_SW") (class "Default")
      (node (ref "ENC1") (pin "2") (pinfunction "NO_2") (pintype "bidirectional"))
      (node (ref "IC9") (pin "21") (pinfunction "MTDO_21") (pintype "bidirectional"))
      (node (ref "R36") (pin "2") (pinfunction "2_2") (pintype "passive"))
    )
    (net (code "11") (name "16-SERVO4") (class "Default")
      (node (ref "IC9") (pin "25") (pinfunction "GPIO16_25") (pintype "bidirectional"))
      (node (ref "JP15") (pin "1") (pinfunction "1_1") (pintype "passive"))
    )
    (net (code "12") (name "17-SERVO3") (class "Default")
      (node (ref "IC9") (pin "27") (pinfunction "GPIO17_27") (pintype "bidirectional"))
      (node (ref "JP14") (pin "1") (pinfunction "1_1") (pintype "passive"))
    )
    (net (code "13") (name "18-SERVO2") (class "Default")
      (node (ref "IC9") (pin "35") (pinfunction "GPIO18_35") (pintype "bidirectional"))
      (node (ref "JP11") (pin "1") (pinfunction "1_1") (pintype "passive"))
    )
    (net (code "14") (name "19-SERVO1") (class "Default")
      (node (ref "IC9") (pin "38") (pinfunction "GPIO19_38") (pintype "bidirectional"))
      (node (ref "JP12") (pin "1") (pinfunction "1_1") (pintype "passive"))
    )
    (net (code "15") (name "21-SDA") (class "Default")
      (node (ref "DSP1") (pin "D11") (pinfunction "D11_D11") (pintype "bidirectional"))
      (node (ref "DSP1") (pin "D12") (pinfunction "D12_D12") (pintype "bidirectional"))
      (node (ref "IC14") (pin "24") (pinfunction "SDA_24") (pintype "bidirectional"))
      (node (ref "IC9") (pin "42") (pinfunction "GPIO21_42") (pintype "bidirectional"))
      (node (ref "JP17") (pin "4") (pinfunction "4_4") (pintype "passive"))
      (node (ref "JP2") (pin "4") (pinfunction "4_4") (pintype "passive"))
      (node (ref "JP5") (pin "4") (pinfunction "4_4") (pintype "passive"))
      (node (ref "JP7") (pin "4") (pinfunction "4_4") (pintype "passive"))
      (node (ref "JP9") (pin "4") (pinfunction "4_4") (pintype "passive"))
      (node (ref "R23") (pin "1") (pinfunction "1_1") (pintype "passive"))
    )
    (net (code "16") (name "22-SCL") (class "Default")
      (node (ref "DSP1") (pin "D13") (pinfunction "D13_D13") (pintype "bidirectional"))
      (node (ref "IC14") (pin "23") (pinfunction "SCL_23") (pintype "bidirectional"))
      (node (ref "IC9") (pin "39") (pinfunction "GPIO22_39") (pintype "bidirectional"))
      (node (ref "JP17") (pin "2") (pinfunction "2_2") (pintype "passive"))
      (node (ref "JP2") (pin "3") (pinfunction "3_3") (pintype "passive"))
      (node (ref "JP5") (pin "3") (pinfunction "3_3") (pintype "passive"))
      (node (ref "JP7") (pin "3") (pinfunction "3_3") (pintype "passive"))
      (node (ref "JP9") (pin "3") (pinfunction "3_3") (pintype "passive"))
      (node (ref "R24") (pin "1") (pinfunction "1_1") (pintype "passive"))
    )
    (net (code "17") (name "23-PWMA") (class "Default")
      (node (ref "IC5") (pin "23") (pinfunction "PWMA_23") (pintype "bidirectional"))
      (node (ref "IC9") (pin "36") (pinfunction "GPIO23_36") (pintype "bidirectional"))
    )
    (net (code "18") (name "25-PWMB") (class "Default")
      (node (ref "IC5") (pin "15") (pinfunction "PWMB_15") (pintype "bidirectional"))
      (node (ref "IC9") (pin "14") (pinfunction "GPIO25_14") (pintype "bidirectional"))
    )
    (net (code "19") (name "26-METAL_S") (class "Default")
      (node (ref "IC9") (pin "15") (pinfunction "GPIO26_15") (pintype "bidirectional"))
      (node (ref "JP6") (pin "2") (pinfunction "2_2") (pintype "passive"))
      (node (ref "R17") (pin "1") (pinfunction "1_1") (pintype "passive"))
    )
    (net (code "20") (name "27-SHCP") (class "Default")
      (node (ref "IC10") (pin "11") (pinfunction "SHCP_11") (pintype "bidirectional"))
      (node (ref "IC12") (pin "11") (pinfunction "SHCP_11") (pintype "bidirectional"))
      (node (ref "IC13") (pin "11") (pinfunction "SHCP_11") (pintype "bidirectional"))
      (node (ref "IC9") (pin "16") (pinfunction "GPIO27_16") (pintype "bidirectional"))
    )
    (net (code "21") (name "32-STCP") (class "Default")
      (node (ref "IC10") (pin "12") (pinfunction "STCP_12") (pintype "bidirectional"))
      (node (ref "IC12") (pin "12") (pinfunction "STCP_12") (pintype "bidirectional"))
      (node (ref "IC13") (pin "12") (pinfunction "STCP_12") (pintype "bidirectional"))
      (node (ref "IC9") (pin "12") (pinfunction "32K_XP_12") (pintype "bidirectional"))
    )
    (net (code "22") (name "33-DS") (class "Default")
      (node (ref "IC10") (pin "14") (pinfunction "DS_14") (pintype "bidirectional"))
      (node (ref "IC9") (pin "13") (pinfunction "32K_XN_13") (pintype "bidirectional"))
    )
    (net (code "23") (name "34-ENC_B") (class "Default")
      (node (ref "C50") (pin "1") (pinfunction "1_1") (pintype "passive"))
      (node (ref "ENC1") (pin "B1") (pinfunction "CHANNEL_B_B1") (pintype "bidirectional"))
      (node (ref "IC9") (pin "10") (pinfunction "VDET_1_10") (pintype "bidirectional"))
      (node (ref "R38") (pin "2") (pinfunction "2_2") (pintype "passive"))
    )
    (net (code "24") (name "35-ENC_A") (class "Default")
      (node (ref "C47") (pin "1") (pinfunction "1_1") (pintype "passive"))
      (node (ref "ENC1") (pin "A1") (pinfunction "CHANNEL_A_A1") (pintype "bidirectional"))
      (node (ref "IC9") (pin "11") (pinfunction "VDET_2_11") (pintype "bidirectional"))
      (node (ref "R37") (pin "2") (pinfunction "2_2") (pintype "passive"))
    )
    (net (code "25") (name "36-VBAT") (class "Default")
      (node (ref "C24") (pin "1") (pinfunction "1_1") (pintype "passive"))
      (node (ref "IC9") (pin "5") (pinfunction "SENSOR_VP_5") (pintype "bidirectional"))
      (node (ref "R26") (pin "2") (pinfunction "2_2") (pintype "passive"))
      (node (ref "R27") (pin "1") (pinfunction "1_1") (pintype "passive"))
    )
    (net (code "26") (name "39-VOUT") (class "Default")
      (node (ref "C25") (pin "1") (pinfunction "1_1") (pintype "passive"))
      (node (ref "IC8") (pin "1") (pinfunction "COMMON_INPUT/OUTPUT_1") (pintype "bidirectional"))
      (node (ref "IC9") (pin "8") (pinfunction "SENSOR_VN_8") (pintype "bidirectional"))
    )
    (net (code "27") (name "A1") (class "Default")
      (node (ref "IC5") (pin "1") (pinfunction "AO1_1_1") (pintype "bidirectional"))
      (node (ref "IC5") (pin "2") (pinfunction "AO1_2_2") (pintype "bidirectional"))
      (node (ref "JP1") (pin "1") (pinfunction "1_1") (pintype "passive"))
      (node (ref "JP1") (pin "2") (pinfunction "2_2") (pintype "passive"))
    )
    (net (code "28") (name "A2") (class "Default")
      (node (ref "IC5") (pin "5") (pinfunction "AO2_1_5") (pintype "bidirectional"))
      (node (ref "IC5") (pin "6") (pinfunction "AO2_2_6") (pintype "bidirectional"))
      (node (ref "JP1") (pin "3") (pinfunction "3_3") (pintype "passive"))
      (node (ref "JP1") (pin "4") (pinfunction "4_4") (pintype "passive"))
    )
    (net (code "29") (name "AE1") (class "Default")
      (node (ref "IC8") (pin "23") (pinfunction "I8_23") (pintype "bidirectional"))
      (node (ref "JP16") (pin "2") (pinfunction "2_2") (pintype "passive"))
    )
    (net (code "30") (name "AE2") (class "Default")
      (node (ref "IC8") (pin "22") (pinfunction "I9_22") (pintype "bidirectional"))
      (node (ref "JP16") (pin "4") (pinfunction "4_4") (pintype "passive"))
    )
    (net (code "31") (name "AE3") (class "Default")
      (node (ref "IC8") (pin "21") (pinfunction "I10_21") (pintype "bidirectional"))
      (node (ref "JP16") (pin "6") (pinfunction "6_6") (pintype "passive"))
    )
    (net (code "32") (name "AIN1") (class "Default")
      (node (ref "IC10") (pin "15") (pinfunction "Q0_15") (pintype "bidirectional"))
      (node (ref "IC5") (pin "21") (pinfunction "AIN1_21") (pintype "bidirectional"))
    )
    (net (code "33") (name "AIN2") (class "Default")
      (node (ref "IC10") (pin "1") (pinfunction "Q1_1") (pintype "bidirectional"))
      (node (ref "IC5") (pin "22") (pinfunction "AIN2_22") (pintype "bidirectional"))
    )
    (net (code "34") (name "B1") (class "Default")
      (node (ref "IC5") (pin "11") (pinfunction "BO1_1_11") (pintype "bidirectional"))
      (node (ref "IC5") (pin "12") (pinfunction "BO1_2_12") (pintype "bidirectional"))
      (node (ref "JP1") (pin "7") (pinfunction "7_7") (pintype "passive"))
      (node (ref "JP1") (pin "8") (pinfunction "8_8") (pintype "passive"))
    )
    (net (code "35") (name "B2") (class "Default")
      (node (ref "IC5") (pin "7") (pinfunction "BO2_1_7") (pintype "bidirectional"))
      (node (ref "IC5") (pin "8") (pinfunction "BO2_2_8") (pintype "bidirectional"))
      (node (ref "JP1") (pin "5") (pinfunction "5_5") (pintype "passive"))
      (node (ref "JP1") (pin "6") (pinfunction "6_6") (pintype "passive"))
    )
    (net (code "36") (name "BIN1") (class "Default")
      (node (ref "IC10") (pin "2") (pinfunction "Q2_2") (pintype "bidirectional"))
      (node (ref "IC5") (pin "17") (pinfunction "BIN1_17") (pintype "bidirectional"))
    )
    (net (code "37") (name "BIN2") (class "Default")
      (node (ref "IC10") (pin "3") (pinfunction "Q3_3") (pintype "bidirectional"))
      (node (ref "IC5") (pin "16") (pinfunction "BIN2_16") (pintype "bidirectional"))
    )
    (net (code "38") (name "CP3V3") (class "Default")
      (node (ref "C10") (pin "2") (pinfunction "2_2") (pintype "passive"))
      (node (ref "C12") (pin "2") (pinfunction "2_2") (pintype "passive"))
      (node (ref "IC4") (pin "5") (pinfunction "VIO_5") (pintype "bidirectional"))
      (node (ref "IC4") (pin "6") (pinfunction "VDD_6") (pintype "bidirectional"))
      (node (ref "R5") (pin "1") (pinfunction "1_1") (pintype "passive"))
      (node (ref "TP7") (pin "1") (pinfunction "1_1") (pintype "bidirectional"))
    )
    (net (code "39") (name "D+") (class "Default")
      (node (ref "D1") (pin "3") (pinfunction "K_2_3") (pintype "bidirectional"))
      (node (ref "IC4") (pin "3") (pinfunction "D+_3") (pintype "bidirectional"))
      (node (ref "TP5") (pin "1") (pinfunction "1_1") (pintype "bidirectional"))
      (node (ref "U1") (pin "A6") (pinfunction "D+_A6") (pintype "bidirectional"))
      (node (ref "U1") (pin "B6") (pinfunction "D+_B6") (pintype "bidirectional"))
    )
    (net (code "40") (name "D-") (class "Default")
      (node (ref "D1") (pin "4") (pinfunction "K_3_4") (pintype "bidirectional"))
      (node (ref "IC4") (pin "4") (pinfunction "D-_4") (pintype "bidirectional"))
      (node (ref "TP6") (pin "1") (pinfunction "1_1") (pintype "bidirectional"))
      (node (ref "U1") (pin "A7") (pinfunction "D-_A7") (pintype "bidirectional"))
      (node (ref "U1") (pin "B7") (pinfunction "D-_B7") (pintype "bidirectional"))
    )
    (net (code "41") (name "DE1") (class "Default")
      (node (ref "IC13") (pin "3") (pinfunction "Q3_3") (pintype "bidirectional"))
      (node (ref "JP16") (pin "1") (pinfunction "1_1") (pintype "passive"))
    )
    (net (code "42") (name "DE2") (class "Default")
      (node (ref "IC13") (pin "4") (pinfunction "Q4_4") (pintype "bidirectional"))
      (node (ref "JP16") (pin "3") (pinfunction "3_3") (pintype "passive"))
    )
    (net (code "43") (name "DE3") (class "Default")
      (node (ref "IC13") (pin "5") (pinfunction "Q5_5") (pintype "bidirectional"))
      (node (ref "JP16") (pin "5") (pinfunction "5_5") (pintype "passive"))
    )
    (net (code "44") (name "DTR") (class "Default")
      (node (ref "IC4") (pin "23") (pinfunction "DTR_23") (pintype "bidirectional"))
      (node (ref "IC6") (pin "4") (pinfunction "E1_4") (pintype "bidirectional"))
      (node (ref "R3") (pin "2") (pinfunction "2_2") (pintype "passive"))
    )
    (net (code "45") (name "FLASH_SCK") (class "Default")
      (node (ref "IC7") (pin "6") (pinfunction "CLK_6") (pintype "bidirectional"))
      (node (ref "IC9") (pin "31") (pinfunction "SD_CLK_31") (pintype "bidirectional"))
    )
    (net (code "46") (name "FLASH_SCS") (class "Default")
      (node (ref "IC7") (pin "1") (pinfunction "~{CS}_1") (pintype "bidirectional"))
      (node (ref "IC9") (pin "30") (pinfunction "SD_CMD_30") (pintype "bidirectional"))
    )
    (net (code "47") (name "FLASH_SDI") (class "Default")
      (node (ref "IC7") (pin "5") (pinfunction "DI(IO0)_5") (pintype "bidirectional"))
      (node (ref "IC9") (pin "33") (pinfunction "SD_DATA_1_33") (pintype "bidirectional"))
    )
    (net (code "48") (name "FLASH_SDO") (class "Default")
      (node (ref "IC7") (pin "2") (pinfunction "DO(IO1)_2") (pintype "bidirectional"))
      (node (ref "IC9") (pin "32") (pinfunction "SD_DATA_0_32") (pintype "bidirectional"))
    )
    (net (code "49") (name "FLASH_SHD") (class "Default")
      (node (ref "IC7") (pin "7") (pinfunction "IO3_7") (pintype "bidirectional"))
      (node (ref "IC9") (pin "28") (pinfunction "SD_DATA_2_28") (pintype "bidirectional"))
    )
    (net (code "50") (name "FLASH_SWP") (class "Default")
      (node (ref "IC7") (pin "3") (pinfunction "IO2_3") (pintype "bidirectional"))
      (node (ref "IC9") (pin "29") (pinfunction "SD_DATA_3_29") (pintype "bidirectional"))
    )
    (net (code "51") (name "FLASH_VDD") (class "Default")
      (node (ref "C21") (pin "2") (pinfunction "2_2") (pintype "passive"))
      (node (ref "C22") (pin "2") (pinfunction "2_2") (pintype "passive"))
      (node (ref "IC7") (pin "8") (pinfunction "VCC_8") (pintype "bidirectional"))
      (node (ref "IC9") (pin "26") (pinfunction "VDD_SDIO_26") (pintype "bidirectional"))
    )
    (net (code "52") (name "GND") (class "Default")
      (node (ref "C1") (pin "2") (pinfunction "2_2") (pintype "passive"))
      (node (ref "C10") (pin "1") (pinfunction "1_1") (pintype "passive"))
      (node (ref "C11") (pin "1") (pinfunction "1_1") (pintype "passive"))
      (node (ref "C12") (pin "1") (pinfunction "1_1") (pintype "passive"))
      (node (ref "C13") (pin "1") (pinfunction "1_1") (pintype "passive"))
      (node (ref "C14") (pin "1") (pinfunction "1_1") (pintype "passive"))
      (node (ref "C15") (pin "2") (pinfunction "2_2") (pintype "passive"))
      (node (ref "C16") (pin "1") (pinfunction "1_1") (pintype "passive"))
      (node (ref "C17") (pin "1") (pinfunction "1_1") (pintype "passive"))
      (node (ref "C18") (pin "1") (pinfunction "1_1") (pintype "passive"))
      (node (ref "C19") (pin "1") (pinfunction "1_1") (pintype "passive"))
      (node (ref "C2") (pin "2") (pinfunction "2_2") (pintype "passive"))
      (node (ref "C20") (pin "1") (pinfunction "1_1") (pintype "passive"))
      (node (ref "C21") (pin "1") (pinfunction "1_1") (pintype "passive"))
      (node (ref "C22") (pin "1") (pinfunction "1_1") (pintype "passive"))
      (node (ref "C26") (pin "1") (pinfunction "1_1") (pintype "passive"))
      (node (ref "C28") (pin "1") (pinfunction "1_1") (pintype "passive"))
      (node (ref "C29") (pin "2") (pinfunction "2_2") (pintype "passive"))
      (node (ref "C3") (pin "2") (pinfunction "2_2") (pintype "passive"))
      (node (ref "C30") (pin "1") (pinfunction "1_1") (pintype "passive"))
      (node (ref "C31") (pin "1") (pinfunction "1_1") (pintype "passive"))
      (node (ref "C33") (pin "2") (pinfunction "2_2") (pintype "passive"))
      (node (ref "C35") (pin "1") (pinfunction "1_1") (pintype "passive"))
      (node (ref "C36") (pin "1") (pinfunction "1_1") (pintype "passive"))
      (node (ref "C37") (pin "2") (pinfunction "2_2") (pintype "passive"))
      (node (ref "C38") (pin "1") (pinfunction "1_1") (pintype "passive"))
      (node (ref "C39") (pin "1") (pinfunction "1_1") (pintype "passive"))
      (node (ref "C4") (pin "2") (pinfunction "2_2") (pintype "passive"))
      (node (ref "C40") (pin "1") (pinfunction "1_1") (pintype "passive"))
      (node (ref "C41") (pin "2") (pinfunction "2_2") (pintype "passive"))
      (node (ref "C44") (pin "2") (pinfunction "2_2") (pintype "passive"))
      (node (ref "C45") (pin "2") (pinfunction "2_2") (pintype "passive"))
      (node (ref "C46") (pin "1") (pinfunction "1_1") (pintype "passive"))
      (node (ref "C47") (pin "2") (pinfunction "2_2") (pintype "passive"))
      (node (ref "C48") (pin "2") (pinfunction "2_2") (pintype "passive"))
      (node (ref "C49") (pin "1") (pinfunction "1_1") (pintype "passive"))
      (node (ref "C5") (pin "2") (pinfunction "-_2") (pintype "bidirectional"))
      (node (ref "C50") (pin "2") (pinfunction "2_2") (pintype "passive"))
      (node (ref "C51") (pin "2") (pinfunction "2_2") (pintype "passive"))
      (node (ref "C6") (pin "2") (pinfunction "2_2") (pintype "passive"))
      (node (ref "C7") (pin "2") (pinfunction "2_2") (pintype "passive"))
      (node (ref "C8") (pin "2") (pinfunction "2_2") (pintype "passive"))
      (node (ref "C9") (pin "2") (pinfunction "2_2") (pintype "passive"))
      (node (ref "CON1") (pin "14") (pinfunction "14_14") (pintype "bidirectional"))
      (node (ref "D1") (pin "1") (pinfunction "COMMON_A_1") (pintype "bidirectional"))
      (node (ref "D3") (pin "2") (pinfunction "A_2") (pintype "bidirectional"))
      (node (ref "DSP1") (pin "D1") (pinfunction "D1_D1") (pintype "bidirectional"))
      (node (ref "DSP1") (pin "D10") (pinfunction "D10_D10") (pintype "bidirectional"))
      (node (ref "DSP1") (pin "D14") (pinfunction "D14_D14") (pintype "bidirectional"))
      (node (ref "DSP1") (pin "D15") (pinfunction "D15_D15") (pintype "bidirectional"))
      (node (ref "DSP1") (pin "D16") (pinfunction "D16_D16") (pintype "bidirectional"))
      (node (ref "DSP1") (pin "D18") (pinfunction "D18_D18") (pintype "bidirectional"))
      (node (ref "DSP1") (pin "D19") (pinfunction "D19_D19") (pintype "bidirectional"))
      (node (ref "DSP1") (pin "D2") (pinfunction "D2_D2") (pintype "bidirectional"))
      (node (ref "DSP1") (pin "D21") (pinfunction "D21_D21") (pintype "bidirectional"))
      (node (ref "DSP1") (pin "D23") (pinfunction "D23_D23") (pintype "bidirectional"))
      (node (ref "DSP1") (pin "D24") (pinfunction "D24_D24") (pintype "bidirectional"))
      (node (ref "DSP1") (pin "D30") (pinfunction "D30_D30") (pintype "bidirectional"))
      (node (ref "DSP1") (pin "D6") (pinfunction "D6_D6") (pintype "bidirectional"))
      (node (ref "DSP1") (pin "D7") (pinfunction "D7_D7") (pintype "bidirectional"))
      (node (ref "DSP1") (pin "D8") (pinfunction "D8_D8") (pintype "bidirectional"))
      (node (ref "DSP1") (pin "D9") (pinfunction "D9_D9") (pintype "bidirectional"))
      (node (ref "ENC1") (pin "C1") (pinfunction "COMMON_C1") (pintype "bidirectional"))
      (node (ref "IC1") (pin "1") (pinfunction "GND_1") (pintype "bidirectional"))
      (node (ref "IC10") (pin "13") (pinfunction "~{OE}_13") (pintype "bidirectional"))
      (node (ref "IC10") (pin "8") (pinfunction "GND_8") (pintype "bidirectional"))
      (node (ref "IC11") (pin "5") (pinfunction "GND_5") (pintype "power_in"))
      (node (ref "IC11") (pin "9") (pinfunction "EP_9") (pintype "bidirectional"))
      (node (ref "IC12") (pin "13") (pinfunction "~{OE}_13") (pintype "bidirectional"))
      (node (ref "IC12") (pin "8") (pinfunction "GND_8") (pintype "bidirectional"))
      (node (ref "IC13") (pin "13") (pinfunction "~{OE}_13") (pintype "bidirectional"))
      (node (ref "IC13") (pin "8") (pinfunction "GND_8") (pintype "bidirectional"))
      (node (ref "IC14") (pin "1") (pinfunction "CLKIN_1") (pintype "bidirectional"))
      (node (ref "IC14") (pin "11") (pinfunction "FSYNC_11") (pintype "bidirectional"))
      (node (ref "IC14") (pin "18") (pinfunction "GND_18") (pintype "bidirectional"))
      (node (ref "IC14") (pin "25") (pinfunction "THERMAL_PAD_25") (pintype "bidirectional"))
      (node (ref "IC2") (pin "1") (pinfunction "GND_1") (pintype "bidirectional"))
      (node (ref "IC3") (pin "1") (pinfunction "GND_1") (pintype "bidirectional"))
      (node (ref "IC4") (pin "2") (pinfunction "GND_2") (pintype "bidirectional"))
      (node (ref "IC4") (pin "25") (pinfunction "EPAD_25") (pintype "bidirectional"))
      (node (ref "IC5") (pin "10") (pinfunction "PGND2_2_10") (pintype "bidirectional"))
      (node (ref "IC5") (pin "18") (pinfunction "GND_18") (pintype "bidirectional"))
      (node (ref "IC5") (pin "3") (pinfunction "PGND1_1_3") (pintype "bidirectional"))
      (node (ref "IC5") (pin "4") (pinfunction "PGND1_2_4") (pintype "bidirectional"))
      (node (ref "IC5") (pin "9") (pinfunction "PGND2_1_9") (pintype "bidirectional"))
      (node (ref "IC7") (pin "4") (pinfunction "GND_1_4") (pintype "bidirectional"))
      (node (ref "IC7") (pin "9") (pinfunction "GND_2_9") (pintype "bidirectional"))
      (node (ref "IC8") (pin "12") (pinfunction "GND_12") (pintype "bidirectional"))
      (node (ref "IC9") (pin "49") (pinfunction "GND_49") (pintype "bidirectional"))
      (node (ref "J1") (pin "2") (pinfunction "2_2") (pintype "bidirectional"))
      (node (ref "J1") (pin "3") (pinfunction "3_3") (pintype "bidirectional"))
      (node (ref "J1") (pin "4") (pinfunction "4_4") (pintype "bidirectional"))
      (node (ref "J1") (pin "5") (pinfunction "5_5") (pintype "bidirectional"))
      (node (ref "J2") (pin "GND") (pinfunction "GND_GND") (pintype "bidirectional"))
      (node (ref "JP11") (pin "3") (pinfunction "3_3") (pintype "passive"))
      (node (ref "JP12") (pin "3") (pinfunction "3_3") (pintype "passive"))
      (node (ref "JP14") (pin "3") (pinfunction "3_3") (pintype "passive"))
      (node (ref "JP15") (pin "3") (pinfunction "3_3") (pintype "passive"))
      (node (ref "JP17") (pin "6") (pinfunction "6_6") (pintype "passive"))
      (node (ref "JP2") (pin "2") (pinfunction "2_2") (pintype "passive"))
      (node (ref "JP3") (pin "1") (pinfunction "1_1") (pintype "passive"))
      (node (ref "JP4") (pin "1") (pinfunction "1_1") (pintype "passive"))
      (node (ref "JP5") (pin "2") (pinfunction "2_2") (pintype "passive"))
      (node (ref "JP6") (pin "1") (pinfunction "1_1") (pintype "passive"))
      (node (ref "JP7") (pin "2") (pinfunction "2_2") (pintype "passive"))
      (node (ref "JP8") (pin "1") (pinfunction "1_1") (pintype "passive"))
      (node (ref "JP9") (pin "2") (pinfunction "2_2") (pintype "passive"))
      (node (ref "L1") (pin "2") (pinfunction "GND_2_2") (pintype "bidirectional"))
      (node (ref "L1") (pin "4") (pinfunction "GND_2_4") (pintype "bidirectional"))
      (node (ref "R1") (pin "2") (pinfunction "2_2") (pintype "passive"))
      (node (ref "R11") (pin "2") (pinfunction "2_2") (pintype "passive"))
      (node (ref "R12") (pin "2") (pinfunction "2_2") (pintype "passive"))
      (node (ref "R15") (pin "2") (pinfunction "2_2") (pintype "passive"))
      (node (ref "R16") (pin "1") (pinfunction "1_1") (pintype "passive"))
      (node (ref "R19") (pin "1") (pinfunction "1_1") (pintype "passive"))
      (node (ref "R2") (pin "2") (pinfunction "2_2") (pintype "passive"))
      (node (ref "R21") (pin "2") (pinfunction "2_2") (pintype "passive"))
      (node (ref "R22") (pin "1") (pinfunction "1_1") (pintype "passive"))
      (node (ref "R27") (pin "2") (pinfunction "2_2") (pintype "passive"))
      (node (ref "R35") (pin "1") (pinfunction "1_1") (pintype "passive"))
      (node (ref "R36") (pin "1") (pinfunction "1_1") (pintype "passive"))
      (node (ref "R6") (pin "2") (pinfunction "2_2") (pintype "passive"))
      (node (ref "SW1") (pin "1_2") (pinfunction "1_2_1_2") (pintype "bidirectional"))
      (node (ref "SW1") (pin "2_2") (pinfunction "2_2_2_2") (pintype "bidirectional"))
      (node (ref "TP4") (pin "1") (pinfunction "1_1") (pintype "bidirectional"))
      (node (ref "U1") (pin "A1B12") (pinfunction "GND_A1B12") (pintype "bidirectional"))
      (node (ref "U1") (pin "B1A12") (pinfunction "GND_B1A12") (pintype "bidirectional"))
      (node (ref "U1") (pin "P$1") (pinfunction "SHLD_P$1") (pintype "bidirectional"))
      (node (ref "U1") (pin "P$10") (pinfunction "SHLD_P$10") (pintype "bidirectional"))
      (node (ref "U1") (pin "P$11") (pinfunction "SHLD_P$11") (pintype "bidirectional"))
      (node (ref "U1") (pin "P$12") (pinfunction "SHLD_P$12") (pintype "bidirectional"))
      (node (ref "U1") (pin "P$14") (pinfunction "SHLD_P$14") (pintype "bidirectional"))
      (node (ref "U1") (pin "P$16") (pinfunction "SHLD_P$16") (pintype "bidirectional"))
      (node (ref "U1") (pin "P$18") (pinfunction "SHLD_P$18") (pintype "bidirectional"))
      (node (ref "U1") (pin "P$2") (pinfunction "SHLD_P$2") (pintype "bidirectional"))
      (node (ref "U1") (pin "P$20") (pinfunction "SHLD_P$20") (pintype "bidirectional"))
      (node (ref "U1") (pin "P$3") (pinfunction "SHLD_P$3") (pintype "bidirectional"))
      (node (ref "U1") (pin "P$4") (pinfunction "SHLD_P$4") (pintype "bidirectional"))
      (node (ref "U1") (pin "P$5") (pinfunction "SHLD_P$5") (pintype "bidirectional"))
      (node (ref "U1") (pin "P$6") (pinfunction "SHLD_P$6") (pintype "bidirectional"))
      (node (ref "U1") (pin "P$7") (pinfunction "SHLD_P$7") (pintype "bidirectional"))
      (node (ref "U1") (pin "P$8") (pinfunction "SHLD_P$8") (pintype "bidirectional"))
      (node (ref "U1") (pin "P$9") (pinfunction "SHLD_P$9") (pintype "bidirectional"))
    )
    (net (code "53") (name "GYRO3V3") (class "Default")
      (node (ref "C49") (pin "2") (pinfunction "2_2") (pintype "passive"))
      (node (ref "C51") (pin "1") (pinfunction "1_1") (pintype "passive"))
      (node (ref "FL3") (pin "2") (pinfunction "2_2") (pintype "bidirectional"))
      (node (ref "IC14") (pin "13") (pinfunction "VDD_13") (pintype "bidirectional"))
      (node (ref "IC14") (pin "8") (pinfunction "VLOGIC_8") (pintype "bidirectional"))
    )
    (net (code "54") (name "LED_L_BLUE") (class "Default")
      (node (ref "IC12") (pin "3") (pinfunction "Q3_3") (pintype "bidirectional"))
      (node (ref "R34") (pin "2") (pinfunction "2_2") (pintype "passive"))
    )
    (net (code "55") (name "LED_L_GREEN") (class "Default")
      (node (ref "IC12") (pin "2") (pinfunction "Q2_2") (pintype "bidirectional"))
      (node (ref "R30") (pin "2") (pinfunction "2_2") (pintype "passive"))
    )
    (net (code "56") (name "LED_L_RED") (class "Default")
      (node (ref "IC12") (pin "1") (pinfunction "Q1_1") (pintype "bidirectional"))
      (node (ref "R32") (pin "2") (pinfunction "2_2") (pintype "passive"))
    )
    (net (code "57") (name "LED_R_BLUE") (class "Default")
      (node (ref "IC12") (pin "6") (pinfunction "Q6_6") (pintype "bidirectional"))
      (node (ref "R33") (pin "2") (pinfunction "2_2") (pintype "passive"))
    )
    (net (code "58") (name "LED_R_GREEN") (class "Default")
      (node (ref "IC12") (pin "5") (pinfunction "Q5_5") (pintype "bidirectional"))
      (node (ref "R29") (pin "2") (pinfunction "2_2") (pintype "passive"))
    )
    (net (code "59") (name "LED_R_RED") (class "Default")
      (node (ref "IC12") (pin "4") (pinfunction "Q4_4") (pintype "bidirectional"))
      (node (ref "R31") (pin "2") (pinfunction "2_2") (pintype "passive"))
    )
    (net (code "60") (name "Net-(C23-Pad2)") (class "Default")
      (node (ref "C23") (pin "2") (pinfunction "2_2") (pintype "passive"))
      (node (ref "J1") (pin "1") (pinfunction "1_1") (pintype "bidirectional"))
    )
    (net (code "61") (name "Net-(C32-Pad1)") (class "Default")
      (node (ref "C32") (pin "1") (pinfunction "1_1") (pintype "passive"))
      (node (ref "R12") (pin "1") (pinfunction "1_1") (pintype "passive"))
    )
    (net (code "62") (name "Net-(C35-Pad2)") (class "Default")
      (node (ref "C35") (pin "2") (pinfunction "2_2") (pintype "passive"))
      (node (ref "C36") (pin "2") (pinfunction "2_2") (pintype "passive"))
      (node (ref "FL2") (pin "2") (pinfunction "2_2") (pintype "bidirectional"))
      (node (ref "JP10") (pin "1") (pinfunction "1_1") (pintype "passive"))
      (node (ref "L2") (pin "2") (pinfunction "2_2") (pintype "bidirectional"))
      (node (ref "R18") (pin "2") (pinfunction "2_2") (pintype "passive"))
    )
    (net (code "63") (name "Net-(C38-Pad2)") (class "Default")
      (node (ref "C38") (pin "2") (pinfunction "2_2") (pintype "passive"))
      (node (ref "DSP1") (pin "D4") (pinfunction "D4_D4") (pintype "bidirectional"))
    )
    (net (code "64") (name "Net-(C39-Pad2)") (class "Default")
      (node (ref "C39") (pin "2") (pinfunction "2_2") (pintype "passive"))
      (node (ref "C40") (pin "2") (pinfunction "2_2") (pintype "passive"))
      (node (ref "DSP1") (pin "D3") (pinfunction "D3_D3") (pintype "bidirectional"))
    )
    (net (code "65") (name "Net-(C42-Pad1)") (class "Default")
      (node (ref "C42") (pin "1") (pinfunction "1_1") (pintype "passive"))
      (node (ref "DSP1") (pin "D27") (pinfunction "D27_D27") (pintype "bidirectional"))
    )
    (net (code "66") (name "Net-(C42-Pad2)") (class "Default")
      (node (ref "C42") (pin "2") (pinfunction "2_2") (pintype "passive"))
      (node (ref "DSP1") (pin "D26") (pinfunction "D26_D26") (pintype "bidirectional"))
    )
    (net (code "67") (name "Net-(C43-Pad1)") (class "Default")
      (node (ref "C43") (pin "1") (pinfunction "1_1") (pintype "passive"))
      (node (ref "DSP1") (pin "D29") (pinfunction "D29_D29") (pintype "bidirectional"))
    )
    (net (code "68") (name "Net-(C43-Pad2)") (class "Default")
      (node (ref "C43") (pin "2") (pinfunction "2_2") (pintype "passive"))
      (node (ref "DSP1") (pin "D28") (pinfunction "D28_D28") (pintype "bidirectional"))
    )
    (net (code "69") (name "Net-(C44-Pad1)") (class "Default")
      (node (ref "C44") (pin "1") (pinfunction "1_1") (pintype "passive"))
      (node (ref "DSP1") (pin "D17") (pinfunction "D17_D17") (pintype "bidirectional"))
      (node (ref "DSP1") (pin "D20") (pinfunction "D20_D20") (pintype "bidirectional"))
      (node (ref "R28") (pin "1") (pinfunction "1_1") (pintype "passive"))
    )
    (net (code "70") (name "Net-(D1-K_1)") (class "Default")
      (node (ref "D1") (pin "2") (pinfunction "K_1_2") (pintype "bidirectional"))
      (node (ref "F1") (pin "1") (pinfunction "1_1") (pintype "bidirectional"))
      (node (ref "TP3") (pin "1") (pinfunction "1_1") (pintype "bidirectional"))
      (node (ref "U1") (pin "A4B9") (pinfunction "VBUS_A4B9") (pintype "bidirectional"))
      (node (ref "U1") (pin "B4A9") (pinfunction "VBUS_B4A9") (pintype "bidirectional"))
    )
    (net (code "71") (name "Net-(D2-A)") (class "Default")
      (node (ref "D2") (pin "2") (pinfunction "A_2") (pintype "bidirectional"))
      (node (ref "F1") (pin "2") (pinfunction "2_2") (pintype "bidirectional"))
    )
    (net (code "72") (name "Net-(D3-K)") (class "Default")
      (node (ref "C34") (pin "2") (pinfunction "2_2") (pintype "passive"))
      (node (ref "D3") (pin "1") (pinfunction "K_1") (pintype "bidirectional"))
      (node (ref "IC11") (pin "1") (pinfunction "SW_1") (pintype "output"))
      (node (ref "L2") (pin "1") (pinfunction "1_1") (pintype "bidirectional"))
    )
    (net (code "73") (name "Net-(D4-A)") (class "Default")
      (node (ref "D4") (pin "2") (pinfunction "A_2") (pintype "bidirectional"))
      (node (ref "Q1") (pin "1") (pinfunction "G_1") (pintype "bidirectional"))
      (node (ref "R22") (pin "2") (pinfunction "2_2") (pintype "passive"))
    )
    (net (code "74") (name "Net-(D4-K)") (class "Default")
      (node (ref "D4") (pin "1") (pinfunction "K_1") (pintype "bidirectional"))
      (node (ref "JP13") (pin "1") (pinfunction "1_1") (pintype "passive"))
      (node (ref "Q1") (pin "2") (pinfunction "S_2") (pintype "bidirectional"))
      (node (ref "Q2") (pin "2") (pinfunction "S_2") (pintype "bidirectional"))
      (node (ref "R25") (pin "1") (pinfunction "1_1") (pintype "passive"))
    )
    (net (code "75") (name "Net-(DSP1-PadD5)") (class "Default")
      (node (ref "DSP1") (pin "D5") (pinfunction "D5_D5") (pintype "bidirectional"))
      (node (ref "R21") (pin "1") (pinfunction "1_1") (pintype "passive"))
    )
    (net (code "76") (name "Net-(F2-Pad2)") (class "Default")
      (node (ref "F2") (pin "2") (pinfunction "2_2") (pintype "bidirectional"))
      (node (ref "FL1") (pin "1") (pinfunction "1_1") (pintype "bidirectional"))
    )
    (net (code "77") (name "Net-(IC1-VOUT_1)") (class "Default")
      (node (ref "C4") (pin "1") (pinfunction "1_1") (pintype "passive"))
      (node (ref "C7") (pin "1") (pinfunction "1_1") (pintype "passive"))
      (node (ref "C9") (pin "1") (pinfunction "1_1") (pintype "passive"))
      (node (ref "FL1") (pin "2") (pinfunction "2_2") (pintype "bidirectional"))
      (node (ref "IC1") (pin "2") (pinfunction "VOUT_1_2") (pintype "bidirectional"))
      (node (ref "IC1") (pin "4") (pinfunction "VOUT_2_4") (pintype "bidirectional"))
    )
    (net (code "78") (name "Net-(IC2-VOUT_1)") (class "Default")
      (node (ref "C6") (pin "1") (pinfunction "1_1") (pintype "passive"))
      (node (ref "C8") (pin "1") (pinfunction "1_1") (pintype "passive"))
      (node (ref "F3") (pin "2") (pinfunction "2_2") (pintype "bidirectional"))
      (node (ref "IC2") (pin "2") (pinfunction "VOUT_1_2") (pintype "bidirectional"))
      (node (ref "IC2") (pin "4") (pinfunction "VOUT_2_4") (pintype "bidirectional"))
    )
    (net (code "79") (name "Net-(IC4-RSTB)") (class "Default")
      (node (ref "IC4") (pin "9") (pinfunction "RSTB_9") (pintype "bidirectional"))
      (node (ref "R5") (pin "2") (pinfunction "2_2") (pintype "passive"))
    )
    (net (code "80") (name "Net-(IC4-VBUS)") (class "Default")
      (node (ref "IC4") (pin "8") (pinfunction "VBUS_8") (pintype "bidirectional"))
      (node (ref "R6") (pin "1") (pinfunction "1_1") (pintype "passive"))
      (node (ref "R7") (pin "2") (pinfunction "2_2") (pintype "passive"))
    )
    (net (code "81") (name "Net-(IC6-B1)") (class "Default")
      (node (ref "IC6") (pin "5") (pinfunction "B1_5") (pintype "bidirectional"))
      (node (ref "R4") (pin "2") (pinfunction "2_2") (pintype "passive"))
    )
    (net (code "82") (name "Net-(IC6-B2)") (class "Default")
      (node (ref "IC6") (pin "2") (pinfunction "B2_2") (pintype "bidirectional"))
      (node (ref "R3") (pin "1") (pinfunction "1_1") (pintype "passive"))
    )
    (net (code "83") (name "Net-(IC8-~{E})") (class "Default")
      (node (ref "IC8") (pin "15") (pinfunction "~{E}_15") (pintype "bidirectional"))
      (node (ref "R11") (pin "1") (pinfunction "1_1") (pintype "passive"))
    )
    (net (code "84") (name "Net-(IC9-CAP1)") (class "Default")
      (node (ref "C26") (pin "2") (pinfunction "2_2") (pintype "passive"))
      (node (ref "C27") (pin "1") (pinfunction "1_1") (pintype "passive"))
      (node (ref "IC9") (pin "48") (pinfunction "CAP1_48") (pintype "bidirectional"))
      (node (ref "R10") (pin "2") (pinfunction "2_2") (pintype "passive"))
    )
    (net (code "85") (name "Net-(IC9-CAP2)") (class "Default")
      (node (ref "C27") (pin "2") (pinfunction "2_2") (pintype "passive"))
      (node (ref "IC9") (pin "47") (pinfunction "CAP2_47") (pintype "bidirectional"))
      (node (ref "R10") (pin "1") (pinfunction "1_1") (pintype "passive"))
    )
    (net (code "86") (name "Net-(IC9-LNA_IN)") (class "Default")
      (node (ref "C23") (pin "1") (pinfunction "1_1") (pintype "passive"))
      (node (ref "IC9") (pin "2") (pinfunction "LNA_IN_2") (pintype "bidirectional"))
    )
    (net (code "87") (name "Net-(IC9-SENSOR_CAPN)") (class "Default")
      (node (ref "C25") (pin "2") (pinfunction "2_2") (pintype "passive"))
      (node (ref "IC9") (pin "7") (pinfunction "SENSOR_CAPN_7") (pintype "bidirectional"))
    )
    (net (code "88") (name "Net-(IC9-SENSOR_CAPP)") (class "Default")
      (node (ref "C24") (pin "2") (pinfunction "2_2") (pintype "passive"))
      (node (ref "IC9") (pin "6") (pinfunction "SENSOR_CAPP_6") (pintype "bidirectional"))
    )
    (net (code "89") (name "Net-(IC9-XTAL_N)") (class "Default")
      (node (ref "C30") (pin "2") (pinfunction "2_2") (pintype "passive"))
      (node (ref "IC9") (pin "44") (pinfunction "XTAL_N_44") (pintype "bidirectional"))
      (node (ref "L1") (pin "3") (pinfunction "CRYSTAL_2_3") (pintype "bidirectional"))
    )
    (net (code "90") (name "Net-(IC9-XTAL_P)") (class "Default")
      (node (ref "C28") (pin "2") (pinfunction "2_2") (pintype "passive"))
      (node (ref "IC9") (pin "45") (pinfunction "XTAL_P_45") (pintype "bidirectional"))
      (node (ref "L1") (pin "1") (pinfunction "CRYSTAL_1_1") (pintype "bidirectional"))
    )
    (net (code "91") (name "Net-(IC10-Q7S)") (class "Default")
      (node (ref "IC10") (pin "9") (pinfunction "Q7S_9") (pintype "bidirectional"))
      (node (ref "IC12") (pin "14") (pinfunction "DS_14") (pintype "bidirectional"))
    )
    (net (code "92") (name "Net-(IC11-BST)") (class "Default")
      (node (ref "C34") (pin "1") (pinfunction "1_1") (pintype "passive"))
      (node (ref "IC11") (pin "8") (pinfunction "BST_8") (pintype "input"))
    )
    (net (code "93") (name "Net-(IC11-COMP)") (class "Default")
      (node (ref "C32") (pin "2") (pinfunction "2_2") (pintype "passive"))
      (node (ref "IC11") (pin "3") (pinfunction "COMP_3") (pintype "bidirectional"))
    )
    (net (code "94") (name "Net-(IC11-EN)") (class "Default")
      (node (ref "IC11") (pin "2") (pinfunction "EN_2") (pintype "input"))
      (node (ref "R13") (pin "1") (pinfunction "1_1") (pintype "passive"))
      (node (ref "R16") (pin "2") (pinfunction "2_2") (pintype "passive"))
    )
    (net (code "95") (name "Net-(IC11-FB)") (class "Default")
      (node (ref "IC11") (pin "4") (pinfunction "FB_4") (pintype "input"))
      (node (ref "R18") (pin "1") (pinfunction "1_1") (pintype "passive"))
      (node (ref "R19") (pin "2") (pinfunction "2_2") (pintype "passive"))
    )
    (net (code "96") (name "Net-(IC11-FREQ)") (class "Default")
      (node (ref "IC11") (pin "6") (pinfunction "FREQ_6") (pintype "input"))
      (node (ref "R15") (pin "1") (pinfunction "1_1") (pintype "passive"))
    )
    (net (code "97") (name "Net-(IC12-Q7S)") (class "Default")
      (node (ref "IC12") (pin "9") (pinfunction "Q7S_9") (pintype "bidirectional"))
      (node (ref "IC13") (pin "14") (pinfunction "DS_14") (pintype "bidirectional"))
    )
    (net (code "98") (name "Net-(IC14-AD0)") (class "Default")
      (node (ref "IC14") (pin "9") (pinfunction "AD0_9") (pintype "bidirectional"))
      (node (ref "R35") (pin "2") (pinfunction "2_2") (pintype "passive"))
    )
    (net (code "99") (name "Net-(IC14-CPOUT)") (class "Default")
      (node (ref "C48") (pin "1") (pinfunction "1_1") (pintype "passive"))
      (node (ref "IC14") (pin "20") (pinfunction "CPOUT_20") (pintype "bidirectional"))
    )
    (net (code "100") (name "Net-(IC14-REGOUT)") (class "Default")
      (node (ref "C46") (pin "2") (pinfunction "2_2") (pintype "passive"))
      (node (ref "IC14") (pin "10") (pinfunction "REGOUT_10") (pintype "bidirectional"))
    )
    (net (code "101") (name "Net-(Q1-D)") (class "Default")
      (node (ref "J2") (pin "B+") (pinfunction "B+_B+") (pintype "bidirectional"))
      (node (ref "JP13") (pin "2") (pinfunction "2_2") (pintype "passive"))
      (node (ref "Q1") (pin "3") (pinfunction "D_3") (pintype "bidirectional"))
    )
    (net (code "102") (name "Net-(Q2-G)") (class "Default")
      (node (ref "Q2") (pin "1") (pinfunction "G_1") (pintype "bidirectional"))
      (node (ref "R25") (pin "2") (pinfunction "2_2") (pintype "passive"))
      (node (ref "SW1") (pin "1_1") (pinfunction "1_1_1_1") (pintype "bidirectional"))
      (node (ref "SW1") (pin "2_1") (pinfunction "2_1_2_1") (pintype "bidirectional"))
    )
    (net (code "103") (name "Net-(R29-Pad1)") (class "Default")
      (node (ref "R29") (pin "1") (pinfunction "1_1") (pintype "passive"))
      (node (ref "RGB1") (pin "P3") (pinfunction "P3_P3") (pintype "bidirectional"))
    )
    (net (code "104") (name "Net-(R30-Pad1)") (class "Default")
      (node (ref "R30") (pin "1") (pinfunction "1_1") (pintype "passive"))
      (node (ref "RGB2") (pin "P3") (pinfunction "P3_P3") (pintype "bidirectional"))
    )
    (net (code "105") (name "Net-(R31-Pad1)") (class "Default")
      (node (ref "R31") (pin "1") (pinfunction "1_1") (pintype "passive"))
      (node (ref "RGB1") (pin "P2") (pinfunction "P2_P2") (pintype "bidirectional"))
    )
    (net (code "106") (name "Net-(R32-Pad1)") (class "Default")
      (node (ref "R32") (pin "1") (pinfunction "1_1") (pintype "passive"))
      (node (ref "RGB2") (pin "P2") (pinfunction "P2_P2") (pintype "bidirectional"))
    )
    (net (code "107") (name "Net-(R33-Pad1)") (class "Default")
      (node (ref "R33") (pin "1") (pinfunction "1_1") (pintype "passive"))
      (node (ref "RGB1") (pin "P1") (pinfunction "P1_P1") (pintype "bidirectional"))
    )
    (net (code "108") (name "Net-(R34-Pad1)") (class "Default")
      (node (ref "R34") (pin "1") (pinfunction "1_1") (pintype "passive"))
      (node (ref "RGB2") (pin "P1") (pinfunction "P1_P1") (pintype "bidirectional"))
    )
    (net (code "109") (name "Net-(U1-CC1)") (class "Default")
      (node (ref "R2") (pin "1") (pinfunction "1_1") (pintype "passive"))
      (node (ref "U1") (pin "A5") (pinfunction "CC1_A5") (pintype "bidirectional"))
    )
    (net (code "110") (name "Net-(U1-CC2)") (class "Default")
      (node (ref "R1") (pin "1") (pinfunction "1_1") (pintype "passive"))
      (node (ref "U1") (pin "B5") (pinfunction "CC2_B5") (pintype "bidirectional"))
    )
    (net (code "111") (name "PT_BLUE") (class "Default")
      (node (ref "CON1") (pin "8") (pinfunction "8_8") (pintype "bidirectional"))
      (node (ref "IC12") (pin "15") (pinfunction "Q0_15") (pintype "bidirectional"))
    )
    (net (code "112") (name "PT_GREEN") (class "Default")
      (node (ref "CON1") (pin "9") (pinfunction "9_9") (pintype "bidirectional"))
      (node (ref "IC10") (pin "7") (pinfunction "Q7_7") (pintype "bidirectional"))
      (node (ref "JP4") (pin "6") (pinfunction "6_6") (pintype "passive"))
    )
    (net (code "113") (name "PT_L_0") (class "Default")
      (node (ref "CON1") (pin "5") (pinfunction "5_5") (pintype "bidirectional"))
      (node (ref "IC8") (pin "7") (pinfunction "I2_7") (pintype "bidirectional"))
    )
    (net (code "114") (name "PT_L_1") (class "Default")
      (node (ref "CON1") (pin "6") (pinfunction "6_6") (pintype "bidirectional"))
      (node (ref "IC8") (pin "8") (pinfunction "I1_8") (pintype "bidirectional"))
    )
    (net (code "115") (name "PT_M") (class "Default")
      (node (ref "CON1") (pin "4") (pinfunction "4_4") (pintype "bidirectional"))
      (node (ref "IC8") (pin "6") (pinfunction "I3_6") (pintype "bidirectional"))
    )
    (net (code "116") (name "PT_RED") (class "Default")
      (node (ref "CON1") (pin "10") (pinfunction "10_10") (pintype "bidirectional"))
      (node (ref "IC10") (pin "6") (pinfunction "Q6_6") (pintype "bidirectional"))
      (node (ref "JP4") (pin "4") (pinfunction "4_4") (pintype "passive"))
    )
    (net (code "117") (name "PT_REF_L") (class "Default")
      (node (ref "CON1") (pin "7") (pinfunction "7_7") (pintype "bidirectional"))
      (node (ref "IC8") (pin "9") (pinfunction "I0_9") (pintype "bidirectional"))
    )
    (net (code "118") (name "PT_REF_R") (class "Default")
      (node (ref "CON1") (pin "1") (pinfunction "1_1") (pintype "bidirectional"))
      (node (ref "IC8") (pin "3") (pinfunction "I6_3") (pintype "bidirectional"))
    )
    (net (code "119") (name "PT_RGB") (class "Default")
      (node (ref "IC8") (pin "2") (pinfunction "I7_2") (pintype "bidirectional"))
      (node (ref "JP4") (pin "2") (pinfunction "2_2") (pintype "passive"))
    )
    (net (code "120") (name "PT_R_0") (class "Default")
      (node (ref "CON1") (pin "3") (pinfunction "3_3") (pintype "bidirectional"))
      (node (ref "IC8") (pin "5") (pinfunction "I4_5") (pintype "bidirectional"))
    )
    (net (code "121") (name "PT_R_1") (class "Default")
      (node (ref "CON1") (pin "2") (pinfunction "2_2") (pintype "bidirectional"))
      (node (ref "IC8") (pin "4") (pinfunction "I5_4") (pintype "bidirectional"))
    )
    (net (code "122") (name "PT_WHITE") (class "Default")
      (node (ref "CON1") (pin "11") (pinfunction "11_11") (pintype "bidirectional"))
      (node (ref "IC10") (pin "5") (pinfunction "Q5_5") (pintype "bidirectional"))
    )
    (net (code "123") (name "RESET") (class "Default")
      (node (ref "C14") (pin "2") (pinfunction "2_2") (pintype "passive"))
      (node (ref "IC6") (pin "6") (pinfunction "C2_6") (pintype "bidirectional"))
      (node (ref "IC9") (pin "9") (pinfunction "CHIP_PU_9") (pintype "bidirectional"))
      (node (ref "R9") (pin "1") (pinfunction "1_1") (pintype "passive"))
      (node (ref "TP10") (pin "1") (pinfunction "1_1") (pintype "bidirectional"))
    )
    (net (code "124") (name "RTS") (class "Default")
      (node (ref "IC4") (pin "19") (pinfunction "RTS_19") (pintype "bidirectional"))
      (node (ref "IC6") (pin "1") (pinfunction "E2_1") (pintype "bidirectional"))
      (node (ref "R4") (pin "1") (pinfunction "1_1") (pintype "passive"))
    )
    (net (code "125") (name "SERVO_5V") (class "Default")
      (node (ref "C5") (pin "1") (pinfunction "+_1") (pintype "bidirectional"))
      (node (ref "IC3") (pin "2") (pinfunction "VOUT_1_2") (pintype "bidirectional"))
      (node (ref "IC3") (pin "4") (pinfunction "VOUT_2_4") (pintype "bidirectional"))
      (node (ref "JP11") (pin "2") (pinfunction "2_2") (pintype "passive"))
      (node (ref "JP12") (pin "2") (pinfunction "2_2") (pintype "passive"))
      (node (ref "JP14") (pin "2") (pinfunction "2_2") (pintype "passive"))
      (node (ref "JP15") (pin "2") (pinfunction "2_2") (pintype "passive"))
      (node (ref "TP13") (pin "1") (pinfunction "1_1") (pintype "bidirectional"))
    )
    (net (code "126") (name "STBY") (class "Default")
      (node (ref "IC10") (pin "4") (pinfunction "Q4_4") (pintype "bidirectional"))
      (node (ref "IC5") (pin "19") (pinfunction "STBY_19") (pintype "bidirectional"))
    )
    (net (code "127") (name "U0RXD") (class "Default")
      (node (ref "IC4") (pin "21") (pinfunction "TXD_21") (pintype "bidirectional"))
      (node (ref "IC9") (pin "40") (pinfunction "U0RXD_40") (pintype "bidirectional"))
      (node (ref "TP9") (pin "1") (pinfunction "1_1") (pintype "bidirectional"))
    )
    (net (code "128") (name "U0TXD") (class "Default")
      (node (ref "IC4") (pin "20") (pinfunction "RXD_20") (pintype "bidirectional"))
      (node (ref "IC9") (pin "41") (pinfunction "U0TXD_41") (pintype "bidirectional"))
      (node (ref "TP11") (pin "1") (pinfunction "1_1") (pintype "bidirectional"))
    )
    (net (code "129") (name "VCC") (class "Default")
      (node (ref "C1") (pin "1") (pinfunction "1_1") (pintype "passive"))
      (node (ref "C2") (pin "1") (pinfunction "1_1") (pintype "passive"))
      (node (ref "C3") (pin "1") (pinfunction "1_1") (pintype "passive"))
      (node (ref "C31") (pin "2") (pinfunction "2_2") (pintype "passive"))
      (node (ref "IC1") (pin "3") (pinfunction "VIN_3") (pintype "bidirectional"))
      (node (ref "IC11") (pin "7") (pinfunction "VIN_7") (pintype "power_in"))
      (node (ref "IC2") (pin "3") (pinfunction "VIN_3") (pintype "bidirectional"))
      (node (ref "IC3") (pin "3") (pinfunction "VIN_3") (pintype "bidirectional"))
      (node (ref "JP10") (pin "2") (pinfunction "2_2") (pintype "passive"))
      (node (ref "JP17") (pin "1") (pinfunction "1_1") (pintype "passive"))
      (node (ref "Q2") (pin "3") (pinfunction "D_3") (pintype "bidirectional"))
      (node (ref "R13") (pin "2") (pinfunction "2_2") (pintype "passive"))
      (node (ref "R26") (pin "1") (pinfunction "1_1") (pintype "passive"))
    )
    (net (code "130") (name "VMOT") (class "Default")
      (node (ref "FL2") (pin "1") (pinfunction "1_1") (pintype "bidirectional"))
      (node (ref "IC5") (pin "13") (pinfunction "VM2_13") (pintype "bidirectional"))
      (node (ref "IC5") (pin "14") (pinfunction "VM3_14") (pintype "bidirectional"))
      (node (ref "IC5") (pin "24") (pinfunction "VM1_24") (pintype "bidirectional"))
    )
    (net (code "131") (name "XSHT1") (class "Default")
      (node (ref "IC12") (pin "7") (pinfunction "Q7_7") (pintype "bidirectional"))
      (node (ref "JP2") (pin "5") (pinfunction "5_5") (pintype "passive"))
    )
    (net (code "132") (name "XSHT2") (class "Default")
      (node (ref "IC13") (pin "15") (pinfunction "Q0_15") (pintype "bidirectional"))
      (node (ref "JP5") (pin "5") (pinfunction "5_5") (pintype "passive"))
    )
    (net (code "133") (name "XSHT3") (class "Default")
      (node (ref "IC13") (pin "1") (pinfunction "Q1_1") (pintype "bidirectional"))
      (node (ref "JP7") (pin "5") (pinfunction "5_5") (pintype "passive"))
    )
    (net (code "134") (name "XSHT4") (class "Default")
      (node (ref "IC13") (pin "2") (pinfunction "Q2_2") (pintype "bidirectional"))
      (node (ref "JP9") (pin "5") (pinfunction "5_5") (pintype "passive"))
    )
    (net (code "135") (name "unconnected-(ENC1-PadMH1)") (class "Default")
      (node (ref "ENC1") (pin "MH1") (pinfunction "MH1_MH1") (pintype "bidirectional"))
    )
    (net (code "136") (name "unconnected-(ENC1-PadMH2)") (class "Default")
      (node (ref "ENC1") (pin "MH2") (pinfunction "MH2_MH2") (pintype "bidirectional"))
    )
    (net (code "137") (name "unconnected-(IC4-CTS-Pad18)") (class "Default")
      (node (ref "IC4") (pin "18") (pinfunction "CTS_18") (pintype "bidirectional"))
    )
    (net (code "138") (name "unconnected-(IC4-DCD-Pad24)") (class "Default")
      (node (ref "IC4") (pin "24") (pinfunction "DCD_24") (pintype "bidirectional"))
    )
    (net (code "139") (name "unconnected-(IC4-DSR-Pad22)") (class "Default")
      (node (ref "IC4") (pin "22") (pinfunction "DSR_22") (pintype "bidirectional"))
    )
    (net (code "140") (name "unconnected-(IC4-GPIO.0_{slash}_TXT-Pad14)") (class "Default")
      (node (ref "IC4") (pin "14") (pinfunction "GPIO.0_/_TXT_14") (pintype "bidirectional"))
    )
    (net (code "141") (name "unconnected-(IC4-GPIO.1_{slash}_RXT-Pad13)") (class "Default")
      (node (ref "IC4") (pin "13") (pinfunction "GPIO.1_/_RXT_13") (pintype "bidirectional"))
    )
    (net (code "142") (name "unconnected-(IC4-GPIO.2_{slash}_RS485-Pad12)") (class "Default")
      (node (ref "IC4") (pin "12") (pinfunction "GPIO.2_/_RS485_12") (pintype "bidirectional"))
    )
    (net (code "143") (name "unconnected-(IC4-GPIO.3_{slash}_WAKEUP-Pad11)") (class "Default")
      (node (ref "IC4") (pin "11") (pinfunction "GPIO.3_/_WAKEUP_11") (pintype "bidirectional"))
    )
    (net (code "144") (name "unconnected-(IC4-NC_1-Pad10)") (class "Default")
      (node (ref "IC4") (pin "10") (pinfunction "NC_1_10") (pintype "bidirectional"))
    )
    (net (code "145") (name "unconnected-(IC4-NC_2-Pad16)") (class "Default")
      (node (ref "IC4") (pin "16") (pinfunction "NC_2_16") (pintype "bidirectional"))
    )
    (net (code "146") (name "unconnected-(IC4-RI_{slash}_CLK-Pad1)") (class "Default")
      (node (ref "IC4") (pin "1") (pinfunction "RI_/_CLK_1") (pintype "bidirectional"))
    )
    (net (code "147") (name "unconnected-(IC4-SUSPEND-Pad17)") (class "Default")
      (node (ref "IC4") (pin "17") (pinfunction "SUSPEND_17") (pintype "bidirectional"))
    )
    (net (code "148") (name "unconnected-(IC4-SUSPENDB-Pad15)") (class "Default")
      (node (ref "IC4") (pin "15") (pinfunction "SUSPENDB_15") (pintype "bidirectional"))
    )
    (net (code "149") (name "unconnected-(IC8-I11-Pad20)") (class "Default")
      (node (ref "IC8") (pin "20") (pinfunction "I11_20") (pintype "bidirectional"))
    )
    (net (code "150") (name "unconnected-(IC8-I12-Pad19)") (class "Default")
      (node (ref "IC8") (pin "19") (pinfunction "I12_19") (pintype "bidirectional"))
    )
    (net (code "151") (name "unconnected-(IC8-I13-Pad18)") (class "Default")
      (node (ref "IC8") (pin "18") (pinfunction "I13_18") (pintype "bidirectional"))
    )
    (net (code "152") (name "unconnected-(IC8-I14-Pad17)") (class "Default")
      (node (ref "IC8") (pin "17") (pinfunction "I14_17") (pintype "bidirectional"))
    )
    (net (code "153") (name "unconnected-(IC8-I15-Pad16)") (class "Default")
      (node (ref "IC8") (pin "16") (pinfunction "I15_16") (pintype "bidirectional"))
    )
    (net (code "154") (name "unconnected-(IC13-Q6-Pad6)") (class "Default")
      (node (ref "IC13") (pin "6") (pinfunction "Q6_6") (pintype "bidirectional"))
    )
    (net (code "155") (name "unconnected-(IC13-Q7-Pad7)") (class "Default")
      (node (ref "IC13") (pin "7") (pinfunction "Q7_7") (pintype "bidirectional"))
    )
    (net (code "156") (name "unconnected-(IC13-Q7S-Pad9)") (class "Default")
      (node (ref "IC13") (pin "9") (pinfunction "Q7S_9") (pintype "bidirectional"))
    )
    (net (code "157") (name "unconnected-(IC14-AUX_CL-Pad7)") (class "Default")
      (node (ref "IC14") (pin "7") (pinfunction "AUX_CL_7") (pintype "bidirectional"))
    )
    (net (code "158") (name "unconnected-(IC14-AUX_DA-Pad6)") (class "Default")
      (node (ref "IC14") (pin "6") (pinfunction "AUX_DA_6") (pintype "bidirectional"))
    )
    (net (code "159") (name "unconnected-(IC14-INT-Pad12)") (class "Default")
      (node (ref "IC14") (pin "12") (pinfunction "INT_12") (pintype "bidirectional"))
    )
    (net (code "160") (name "unconnected-(IC14-NC_1-Pad2)") (class "Default")
      (node (ref "IC14") (pin "2") (pinfunction "NC_1_2") (pintype "bidirectional"))
    )
    (net (code "161") (name "unconnected-(IC14-NC_2-Pad3)") (class "Default")
      (node (ref "IC14") (pin "3") (pinfunction "NC_2_3") (pintype "bidirectional"))
    )
    (net (code "162") (name "unconnected-(IC14-NC_3-Pad4)") (class "Default")
      (node (ref "IC14") (pin "4") (pinfunction "NC_3_4") (pintype "bidirectional"))
    )
    (net (code "163") (name "unconnected-(IC14-NC_4-Pad5)") (class "Default")
      (node (ref "IC14") (pin "5") (pinfunction "NC_4_5") (pintype "bidirectional"))
    )
    (net (code "164") (name "unconnected-(IC14-NC_5-Pad14)") (class "Default")
      (node (ref "IC14") (pin "14") (pinfunction "NC_5_14") (pintype "bidirectional"))
    )
    (net (code "165") (name "unconnected-(IC14-NC_6-Pad15)") (class "Default")
      (node (ref "IC14") (pin "15") (pinfunction "NC_6_15") (pintype "bidirectional"))
    )
    (net (code "166") (name "unconnected-(IC14-NC_7-Pad16)") (class "Default")
      (node (ref "IC14") (pin "16") (pinfunction "NC_7_16") (pintype "bidirectional"))
    )
    (net (code "167") (name "unconnected-(IC14-NC_8-Pad17)") (class "Default")
      (node (ref "IC14") (pin "17") (pinfunction "NC_8_17") (pintype "bidirectional"))
    )
    (net (code "168") (name "unconnected-(IC14-RESV_1-Pad19)") (class "Default")
      (node (ref "IC14") (pin "19") (pinfunction "RESV_1_19") (pintype "bidirectional"))
    )
    (net (code "169") (name "unconnected-(IC14-RESV_2-Pad21)") (class "Default")
      (node (ref "IC14") (pin "21") (pinfunction "RESV_2_21") (pintype "bidirectional"))
    )
    (net (code "170") (name "unconnected-(IC14-RESV_3-Pad22)") (class "Default")
      (node (ref "IC14") (pin "22") (pinfunction "RESV_3_22") (pintype "bidirectional"))
    )
  )
)
